# discferret_main.net
KiCad netlist of a schematic drawn in EAGLE
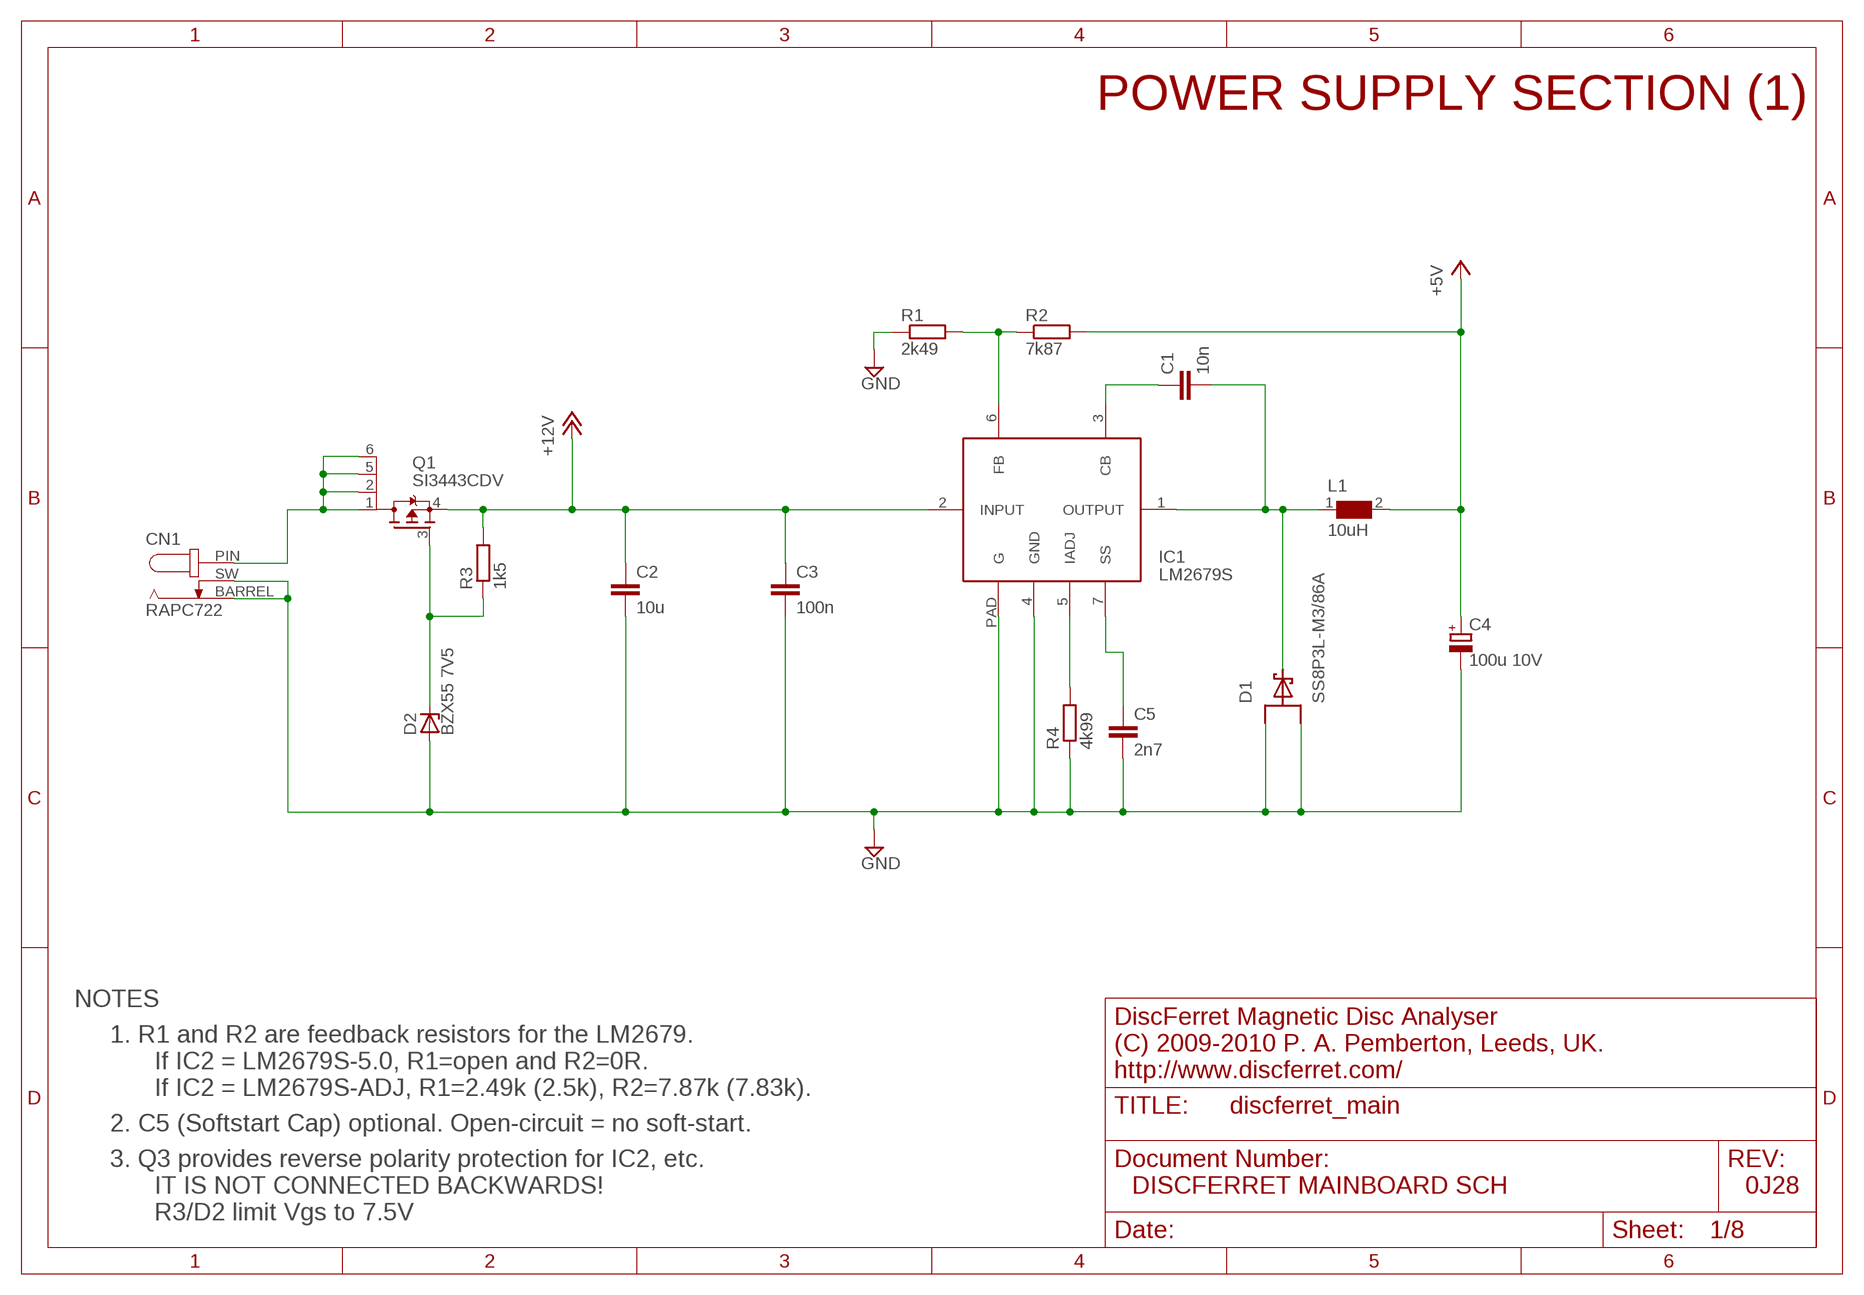
[diagram p0: schematic, sheet 1]
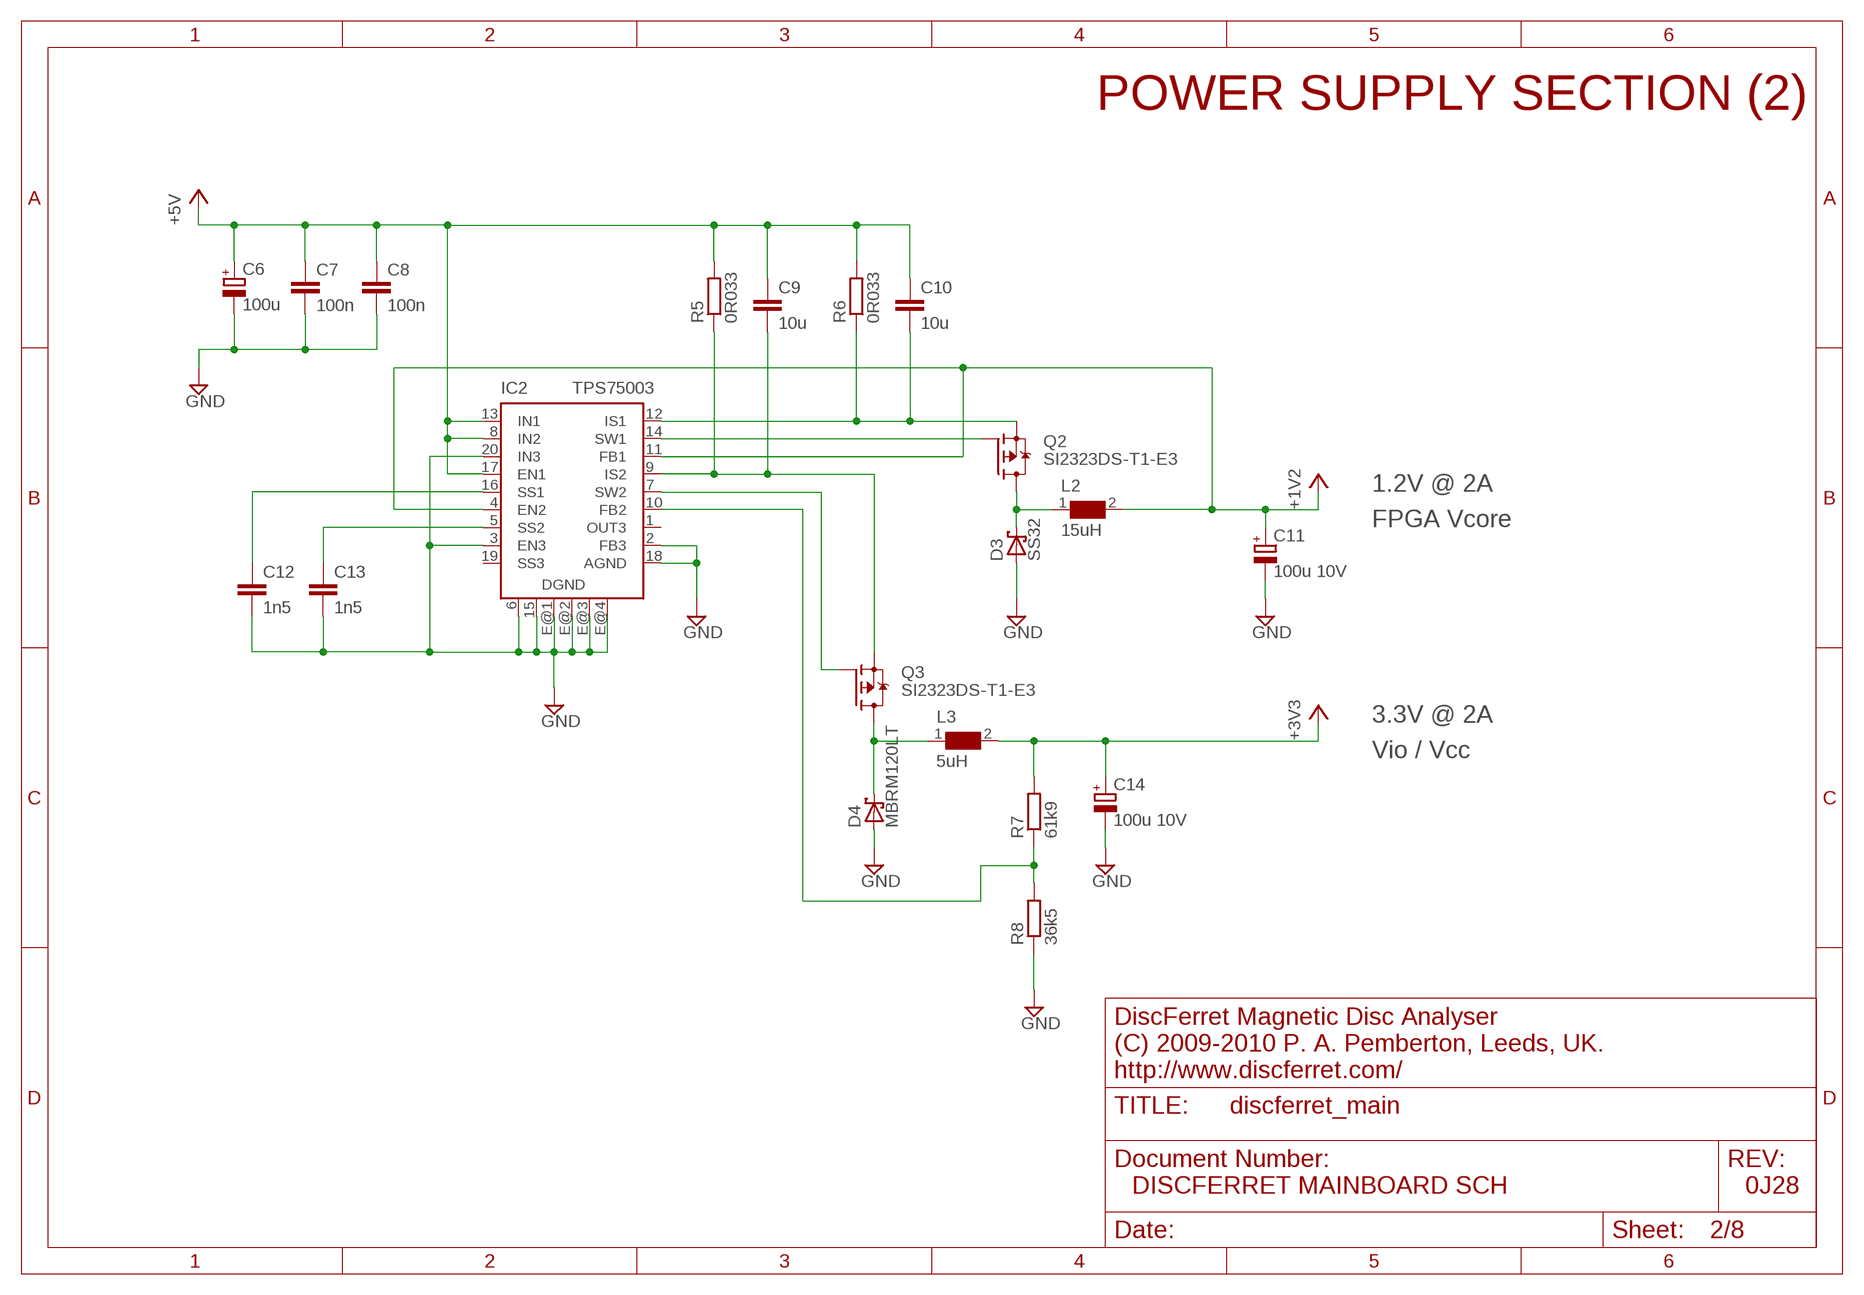
[diagram p1: schematic, sheet 2]
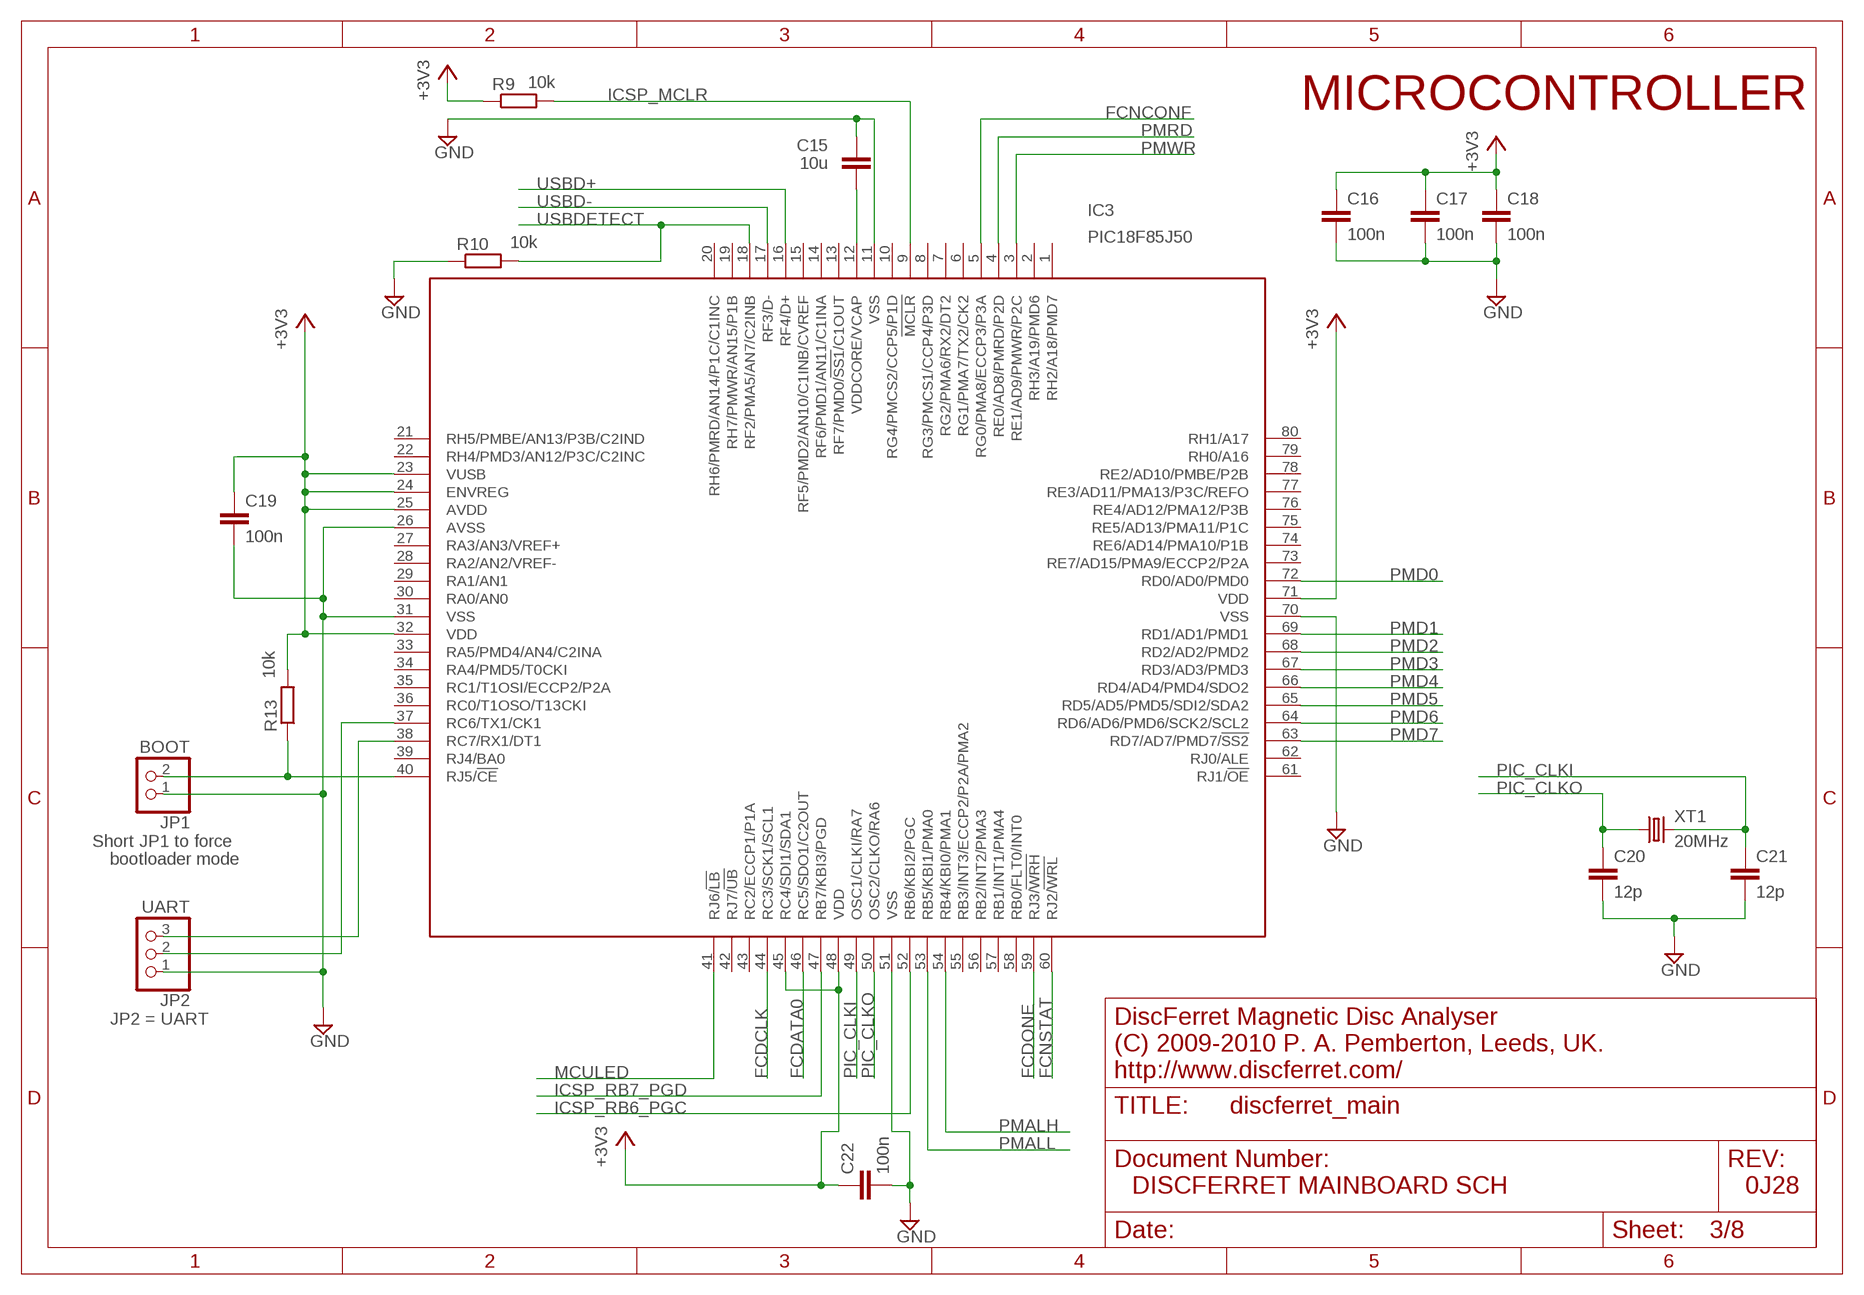
[diagram p2: schematic, sheet 3]
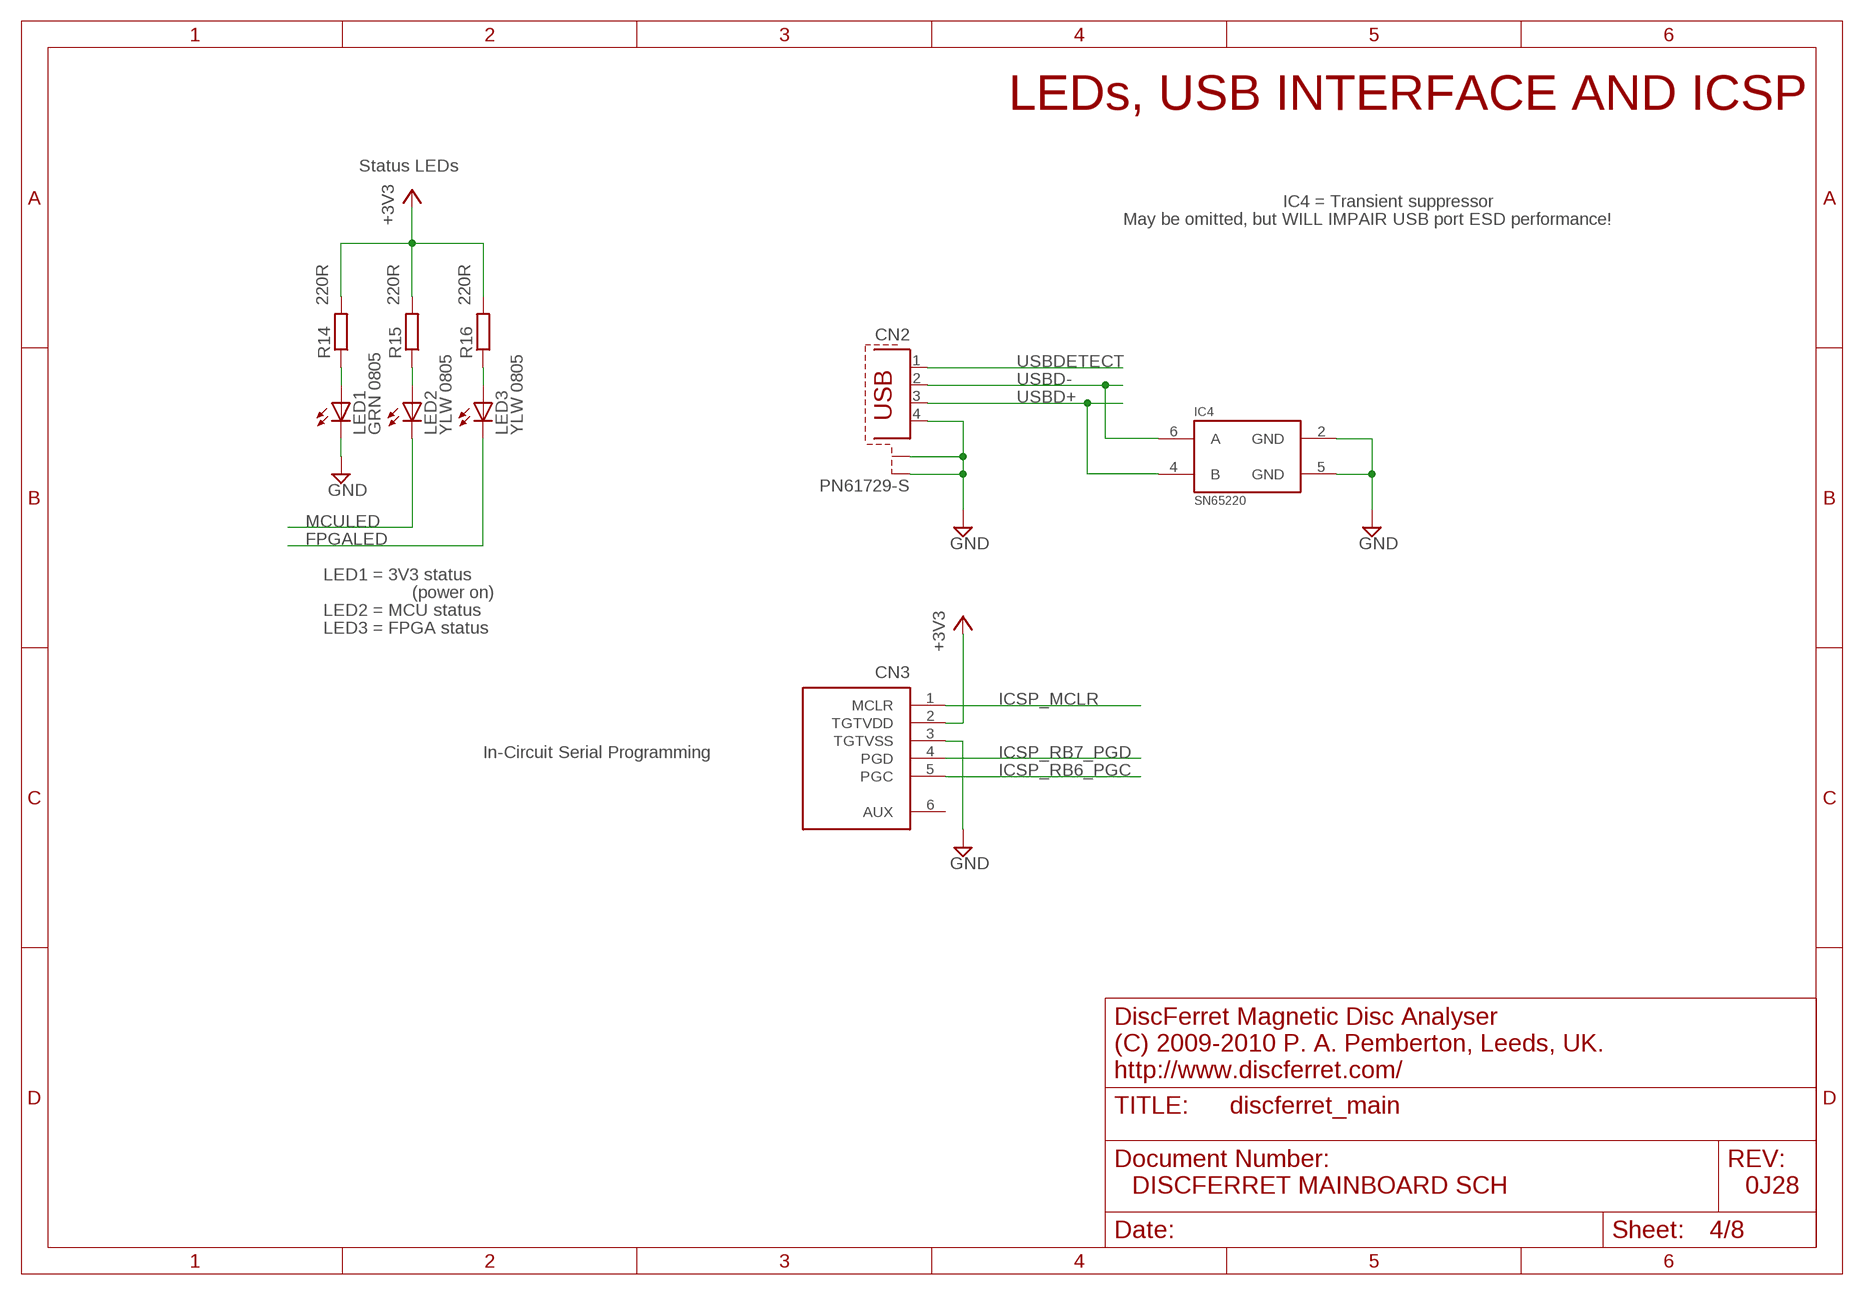
[diagram p3: schematic, sheet 4]
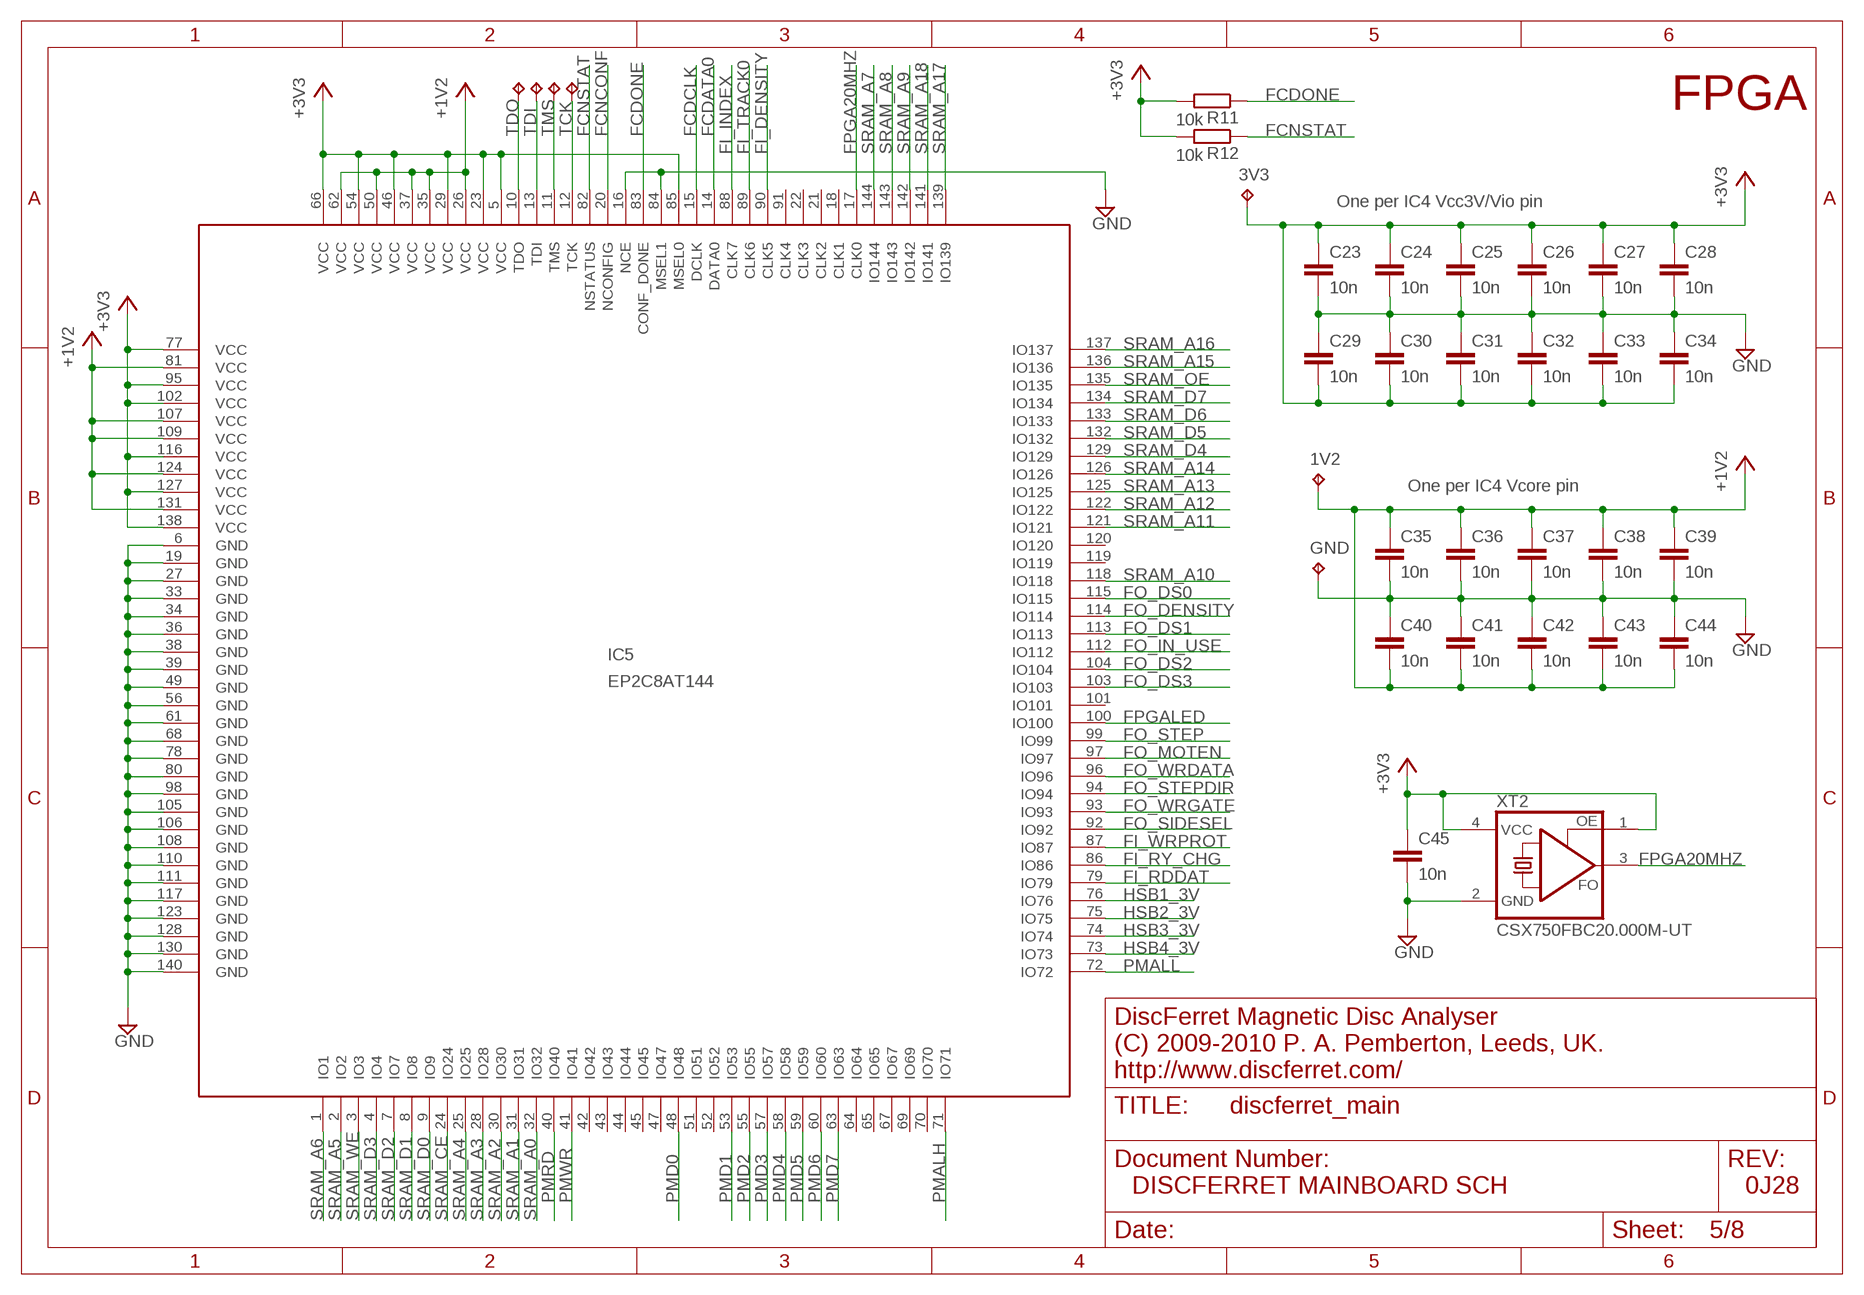
[diagram p4: schematic, sheet 5]
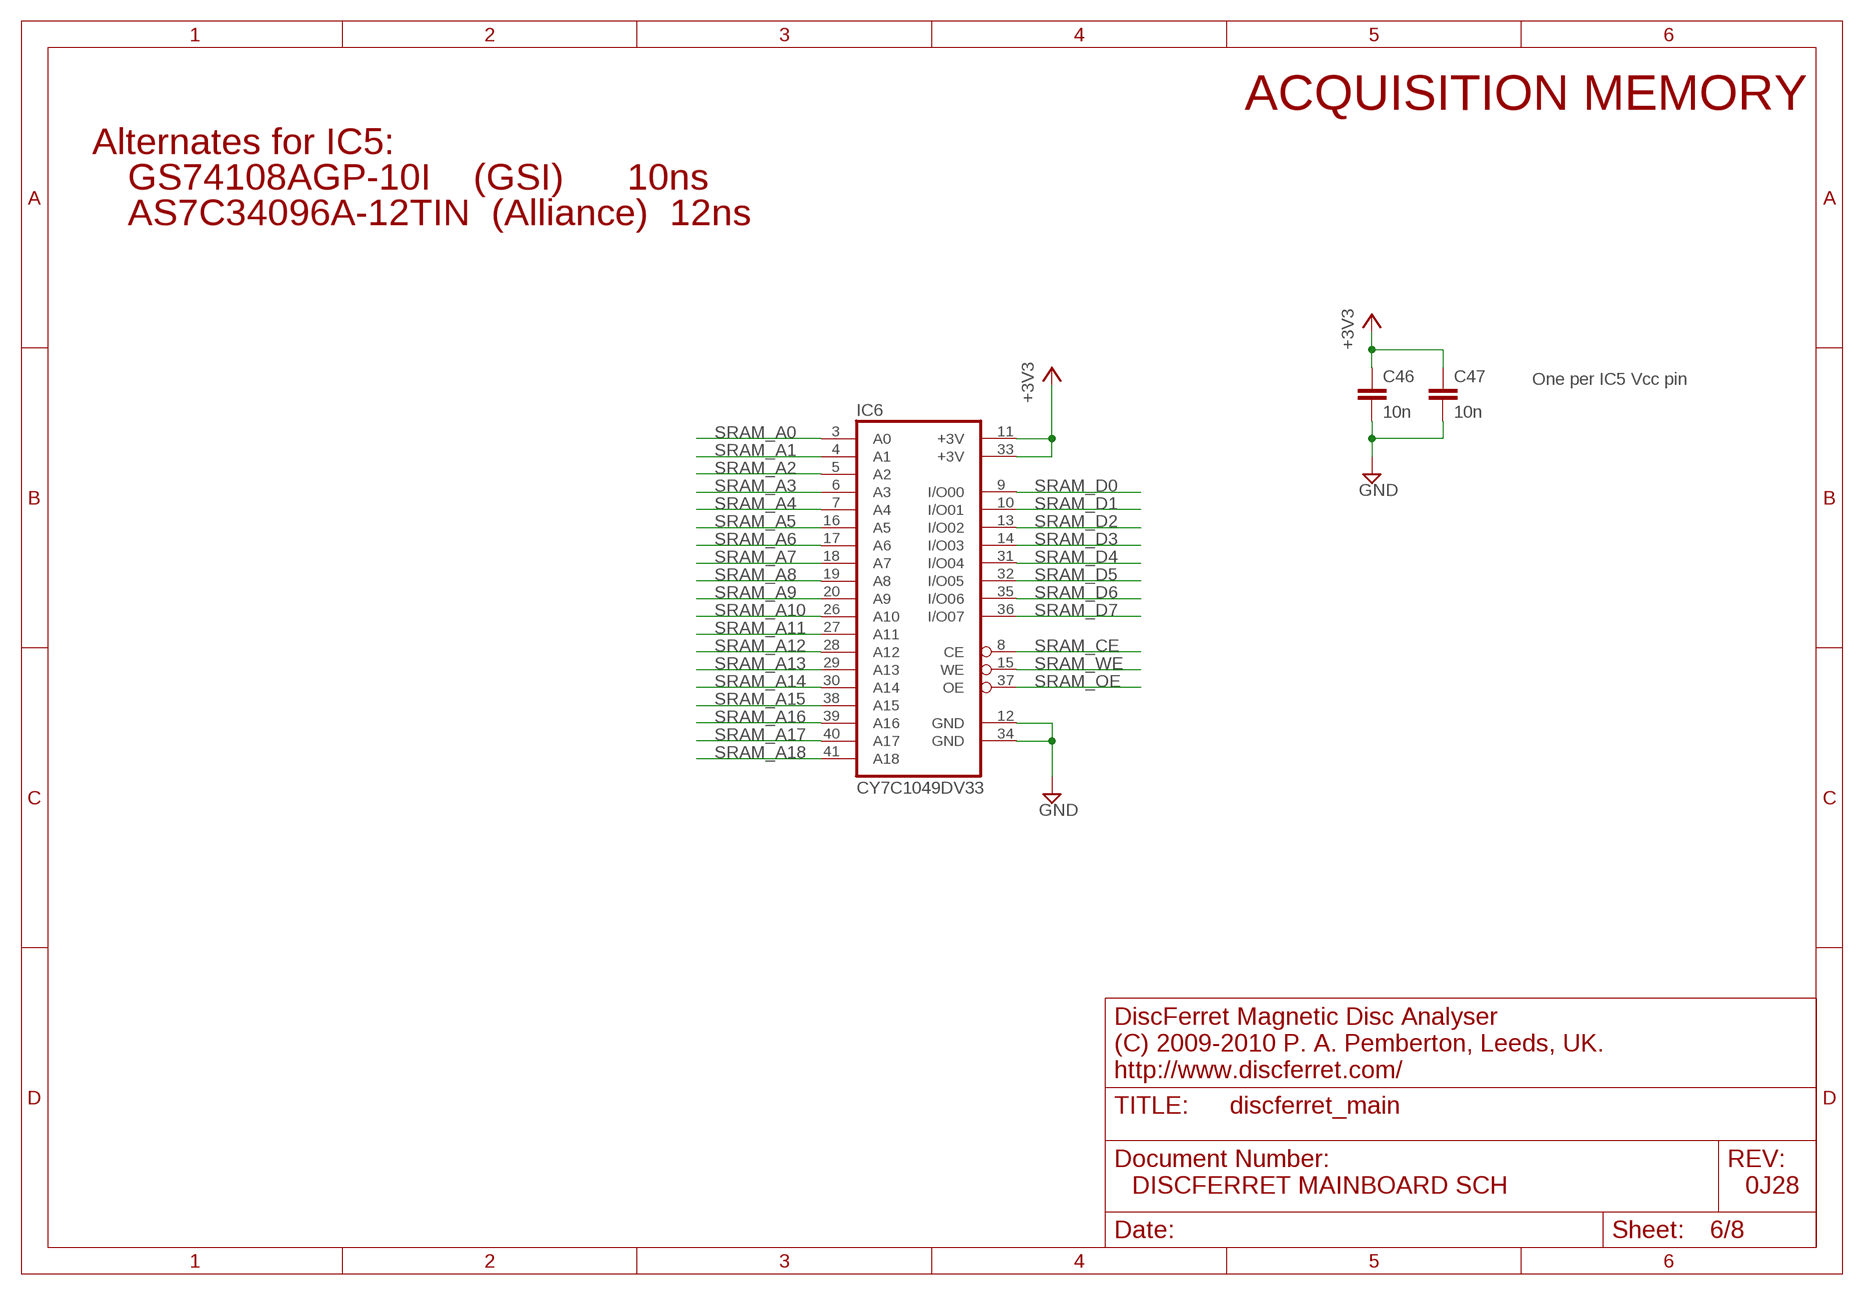
[diagram p5: schematic, sheet 6]
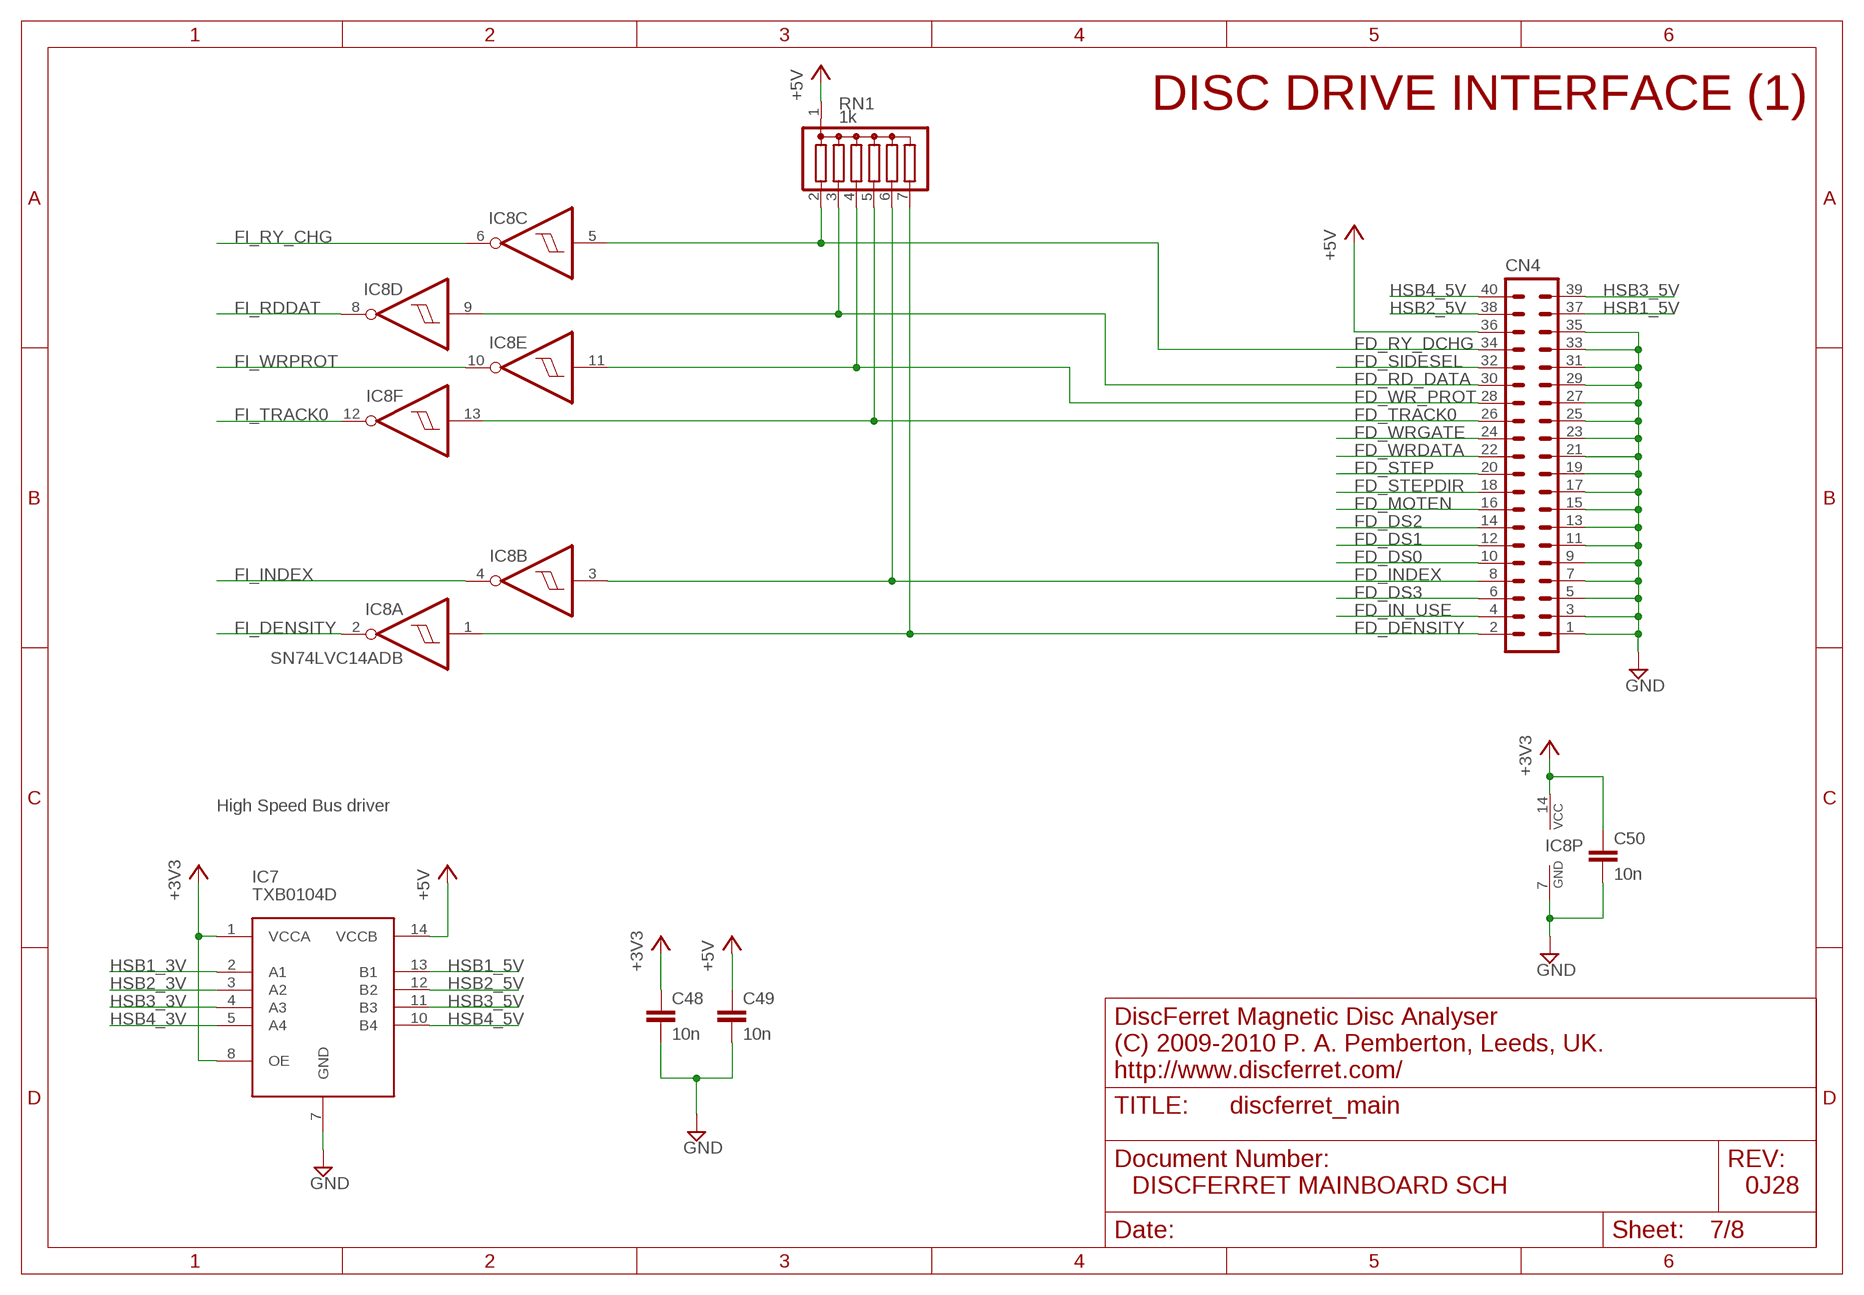
[diagram p6: schematic, sheet 7]
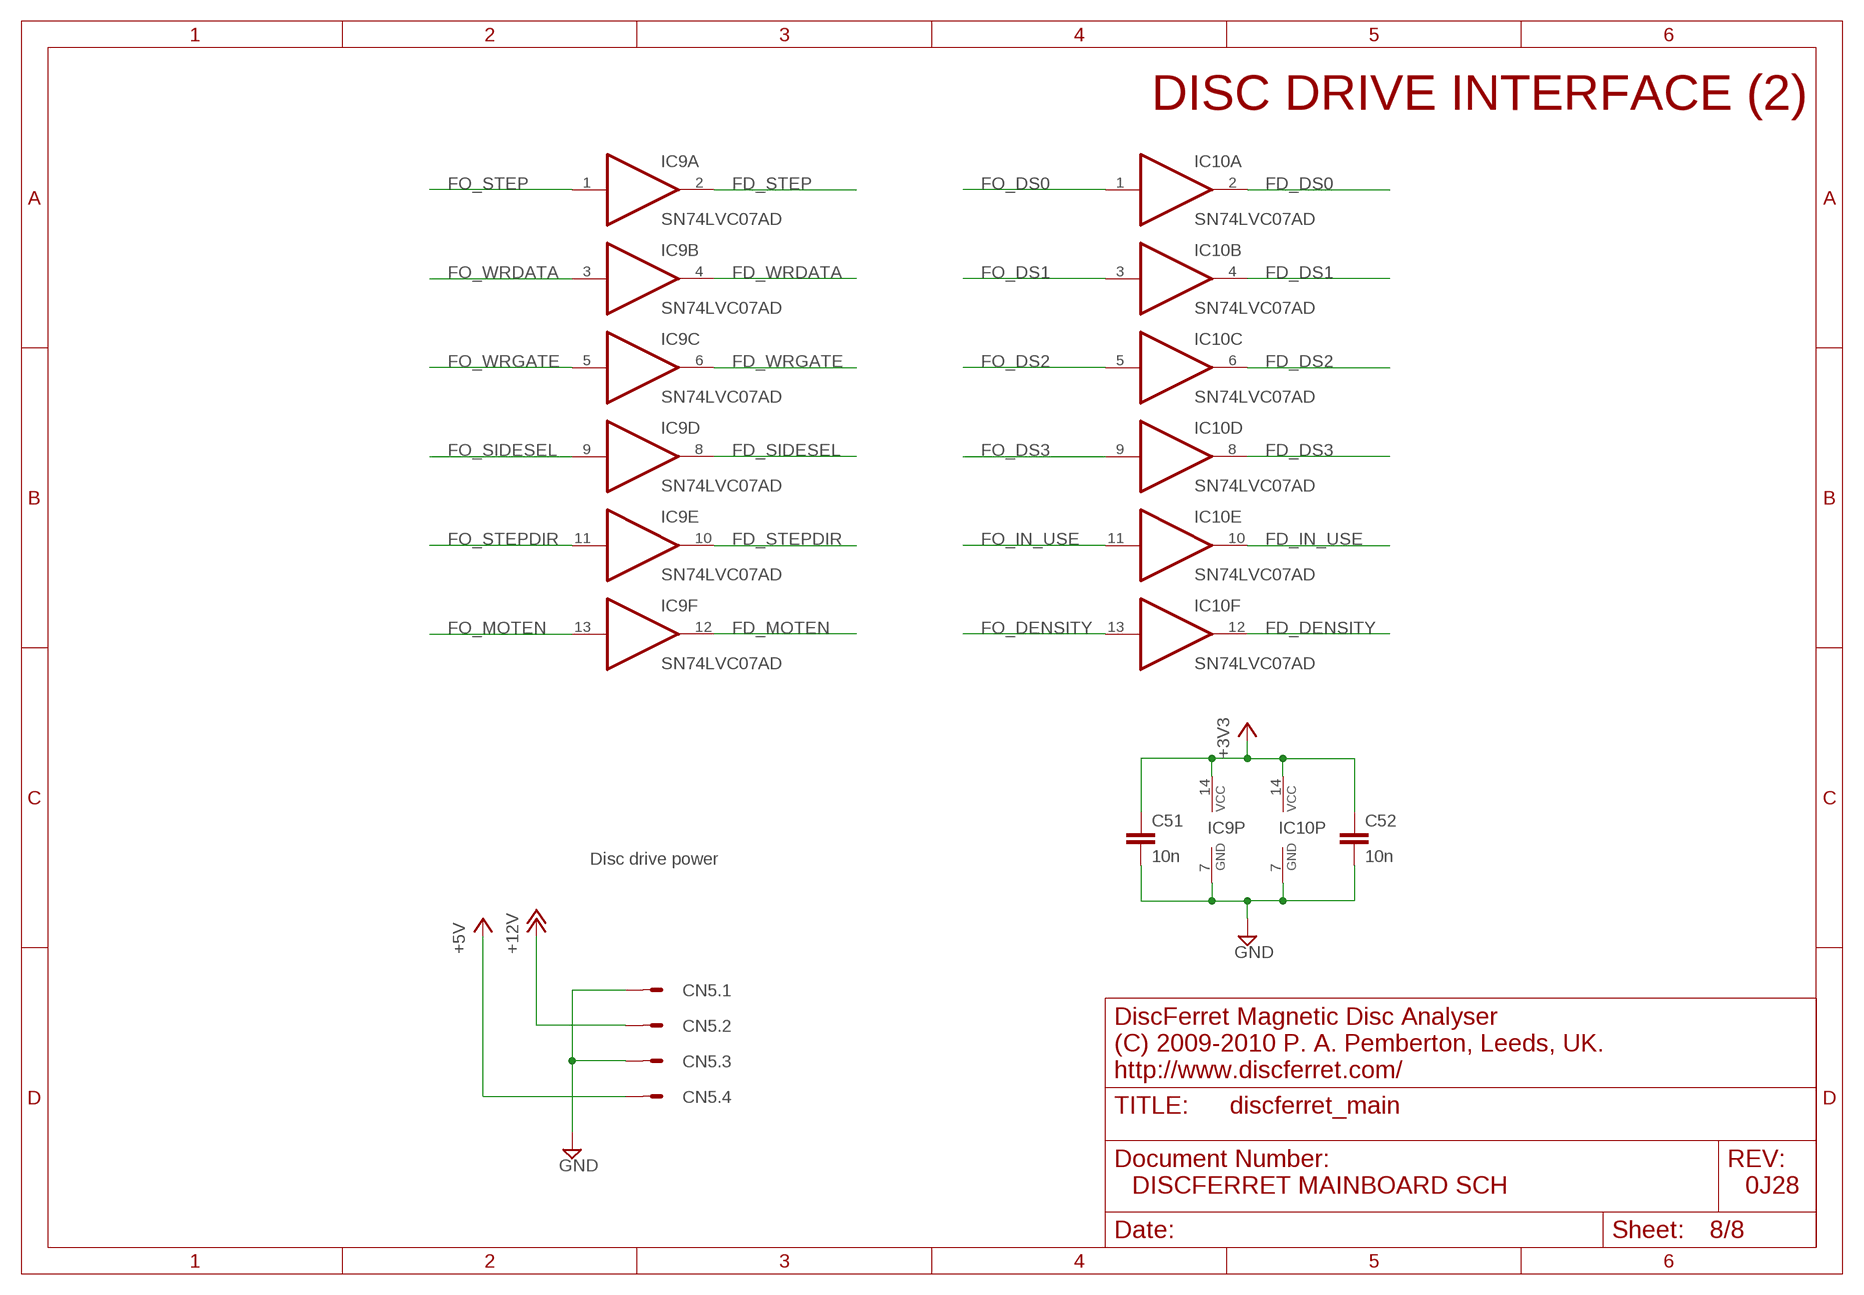
[diagram p7: schematic, sheet 8]

(export (version "E")
  (design (tool "Eeschema 10.0.6"))
  (components
    (comp (ref "C46")
      (value "10n")
      (footprint "eagle-import:C0603")
      (libsource (lib "eagle-import") (part "C-EUC0603"))
    )
    (comp (ref "C47")
      (value "10n")
      (footprint "eagle-import:C0603")
      (libsource (lib "eagle-import") (part "C-EUC0603"))
    )
    (comp (ref "IC6")
      (value "CY7C1049DV33")
      (footprint "eagle-import:TSOPII-Z44")
      (fields (field (name "MANUFACTURER") "Cypress Semiconductor"))
      (libsource (lib "eagle-import") (part "CY7C1049CV33T"))
    )
    (comp (ref "C48")
      (value "10n")
      (footprint "eagle-import:C0603")
      (libsource (lib "eagle-import") (part "C-EUC0603"))
    )
    (comp (ref "C49")
      (value "10n")
      (footprint "eagle-import:C0603")
      (libsource (lib "eagle-import") (part "C-EUC0603"))
    )
    (comp (ref "C50")
      (value "10n")
      (footprint "eagle-import:C0603")
      (libsource (lib "eagle-import") (part "C-EUC0603"))
    )
    (comp (ref "CN4")
      (value "40H")
      (footprint "eagle-import:40H")
      (fields (field (name "MANUFACTURER") "Multicomp"))
      (libsource (lib "eagle-import") (part "40H"))
    )
    (comp (ref "IC7")
      (value "TXB0104D")
      (footprint "eagle-import:SO14")
      (fields (field (name "MANUFACTURER") "Texas Instruments"))
      (libsource (lib "eagle-import") (part "TXB0104D"))
    )
    (comp (ref "IC8")
      (value "SN74LVC14ADB")
      (footprint "eagle-import:SSOP14")
      (fields
        (field (name "MANUF-PN") "SN74LVC14ADB")
        (field (name "MANUFACTURER") "Texas Instruments")
        (field (name "SUPPLIER") "FARNELL")
        (field (name "SUPPLIER-PN") "1236311")
      )
      (libsource (lib "eagle-import") (part "SN74LVC14ADB"))
    )
    (comp (ref "RN1")
      (value "1k")
      (footprint "eagle-import:SIL7")
      (fields (field (name "MANUFACTURER") "Bourns"))
      (libsource (lib "eagle-import") (part "G06R"))
    )
    (comp (ref "C6")
      (value "100u")
      (footprint "eagle-import:SMC_D")
      (fields (field (name "MANUFACTURER") "Vishay Sprague"))
      (libsource (lib "eagle-import") (part "CPOL-EUSMCD"))
    )
    (comp (ref "C7")
      (value "100n")
      (footprint "eagle-import:C0805")
      (libsource (lib "eagle-import") (part "C-EUC0805"))
    )
    (comp (ref "C8")
      (value "100n")
      (footprint "eagle-import:C0805")
      (libsource (lib "eagle-import") (part "C-EUC0805"))
    )
    (comp (ref "C9")
      (value "10u")
      (footprint "eagle-import:C0805")
      (fields (field (name "MANUFACTURER") "Murata"))
      (libsource (lib "eagle-import") (part "C-EUC0805"))
    )
    (comp (ref "C10")
      (value "10u")
      (footprint "eagle-import:C0805")
      (fields (field (name "MANUFACTURER") "Murata"))
      (libsource (lib "eagle-import") (part "C-EUC0805"))
    )
    (comp (ref "C11")
      (value "100u 10V")
      (footprint "eagle-import:SMC_D")
      (fields (field (name "MANUFACTURER") "AVX"))
      (libsource (lib "eagle-import") (part "CPOL-EUSMCD"))
    )
    (comp (ref "C12")
      (value "1n5")
      (footprint "eagle-import:C0805")
      (fields (field (name "MANUFACTURER") "Multicomp"))
      (libsource (lib "eagle-import") (part "C-EUC0805"))
    )
    (comp (ref "C13")
      (value "1n5")
      (footprint "eagle-import:C0805")
      (fields (field (name "MANUFACTURER") "Multicomp"))
      (libsource (lib "eagle-import") (part "C-EUC0805"))
    )
    (comp (ref "C14")
      (value "100u 10V")
      (footprint "eagle-import:SMC_D")
      (fields (field (name "MANUFACTURER") "AVX"))
      (libsource (lib "eagle-import") (part "CPOL-EUSMCD"))
    )
    (comp (ref "D3")
      (value "SS32")
      (footprint "eagle-import:SMC")
      (fields (field (name "MANUFACTURER") "Multicomp"))
      (libsource (lib "eagle-import") (part "SCHOTTKY-DIODESMC"))
    )
    (comp (ref "D4")
      (value "MBRM120LT")
      (footprint "eagle-import:POWERMITE_LARGEPAD")
      (fields (field (name "MANUFACTURER") "ON Semiconductor"))
      (libsource (lib "eagle-import") (part "MBRM120LT-LARGEPAD"))
    )
    (comp (ref "IC2")
      (value "TPS75003")
      (footprint "eagle-import:R-PQFP-N20")
      (fields (field (name "MANUFACTURER") "Texas Instruments"))
      (libsource (lib "eagle-import") (part "TPS75003"))
    )
    (comp (ref "L2")
      (value "15uH")
      (footprint "eagle-import:WE-TPC_XL_XLH")
      (fields (field (name "MANUFACTURER") "Bourns"))
      (libsource (lib "eagle-import") (part "WE-TPC_XL/XLH"))
    )
    (comp (ref "L3")
      (value "5uH")
      (footprint "eagle-import:WE-TPC_XL_XLH")
      (fields (field (name "MANUFACTURER") "Wuerth Elektronik"))
      (libsource (lib "eagle-import") (part "WE-TPC_XL/XLH"))
    )
    (comp (ref "Q2")
      (value "SI2323DS-T1-E3")
      (footprint "eagle-import:SOT23")
      (fields (field (name "MANUFACTURER") "Vishay Siliconix"))
      (libsource (lib "eagle-import") (part "SI2323DS-T1-E3"))
    )
    (comp (ref "Q3")
      (value "SI2323DS-T1-E3")
      (footprint "eagle-import:SOT23")
      (fields (field (name "MANUFACTURER") "Vishay Siliconix"))
      (libsource (lib "eagle-import") (part "SI2323DS-T1-E3"))
    )
    (comp (ref "R5")
      (value "0R033")
      (footprint "eagle-import:R1206")
      (fields (field (name "MANUFACTURER") "Welwyn"))
      (libsource (lib "eagle-import") (part "R-EU_R1206"))
    )
    (comp (ref "R6")
      (value "0R033")
      (footprint "eagle-import:R1206")
      (fields (field (name "MANUFACTURER") "Welwyn"))
      (libsource (lib "eagle-import") (part "R-EU_R1206"))
    )
    (comp (ref "R7")
      (value "61k9")
      (footprint "eagle-import:R0805")
      (libsource (lib "eagle-import") (part "R-EU_R0805"))
    )
    (comp (ref "R8")
      (value "36k5")
      (footprint "eagle-import:R0603")
      (libsource (lib "eagle-import") (part "R-EU_R0603"))
    )
    (comp (ref "C51")
      (value "10n")
      (footprint "eagle-import:C0603")
      (libsource (lib "eagle-import") (part "C-EUC0603"))
    )
    (comp (ref "C52")
      (value "10n")
      (footprint "eagle-import:C0603")
      (libsource (lib "eagle-import") (part "C-EUC0603"))
    )
    (comp (ref "CN5")
      (value "2X2-A")
      (footprint "eagle-import:3-794618-4")
      (libsource (lib "eagle-import") (part "2X2-A"))
    )
    (comp (ref "IC9")
      (value "SN74LVC07AD")
      (footprint "eagle-import:SO14")
      (fields
        (field (name "MANUFACTURER") "Texas Instruments")
        (field (name "SUPPLIER") "FARNELL")
        (field (name "SUPPLIER-PN") "9592660")
        (field (name "MANUF-PN") "SN74LVC07AD")
      )
      (libsource (lib "eagle-import") (part "SN74LVC07AD"))
    )
    (comp (ref "IC10")
      (value "SN74LVC07AD")
      (footprint "eagle-import:SO14")
      (fields
        (field (name "MANUF-PN") "SN74LVC07AD")
        (field (name "MANUFACTURER") "Texas Instruments")
        (field (name "SUPPLIER") "FARNELL")
        (field (name "SUPPLIER-PN") "9592660")
      )
      (libsource (lib "eagle-import") (part "SN74LVC07AD"))
    )
    (comp (ref "C15")
      (value "10u")
      (footprint "eagle-import:C0805")
      (fields (field (name "MANUFACTURER") "Murata"))
      (libsource (lib "eagle-import") (part "C-EUC0805"))
    )
    (comp (ref "C16")
      (value "100n")
      (footprint "eagle-import:C0603")
      (libsource (lib "eagle-import") (part "C-EUC0603"))
    )
    (comp (ref "C17")
      (value "100n")
      (footprint "eagle-import:C0603")
      (libsource (lib "eagle-import") (part "C-EUC0603"))
    )
    (comp (ref "C18")
      (value "100n")
      (footprint "eagle-import:C0603")
      (libsource (lib "eagle-import") (part "C-EUC0603"))
    )
    (comp (ref "C19")
      (value "100n")
      (footprint "eagle-import:C0603")
      (libsource (lib "eagle-import") (part "C-EUC0603"))
    )
    (comp (ref "C20")
      (value "12p")
      (footprint "eagle-import:C0603")
      (libsource (lib "eagle-import") (part "C-EUC0603"))
    )
    (comp (ref "C21")
      (value "12p")
      (footprint "eagle-import:C0603")
      (libsource (lib "eagle-import") (part "C-EUC0603"))
    )
    (comp (ref "C22")
      (value "100n")
      (footprint "eagle-import:C0603")
      (libsource (lib "eagle-import") (part "C-EUC0603"))
    )
    (comp (ref "IC3")
      (value "PIC18F85J50")
      (footprint "eagle-import:TQFP80-12X12")
      (libsource (lib "eagle-import") (part "PIC18F8J505"))
    )
    (comp (ref "JP1")
      (value "BOOT")
      (footprint "eagle-import:1X02")
      (libsource (lib "eagle-import") (part "PINHD-1X2"))
    )
    (comp (ref "JP2")
      (value "UART")
      (footprint "eagle-import:1X03")
      (libsource (lib "eagle-import") (part "PINHD-1X3"))
    )
    (comp (ref "R9")
      (value "10k")
      (footprint "eagle-import:R0805")
      (libsource (lib "eagle-import") (part "R-EU_R0805"))
    )
    (comp (ref "R10")
      (value "10k")
      (footprint "eagle-import:R0805")
      (libsource (lib "eagle-import") (part "R-EU_R0805"))
    )
    (comp (ref "R13")
      (value "10k")
      (footprint "eagle-import:R0805")
      (libsource (lib "eagle-import") (part "R-EU_R0805"))
    )
    (comp (ref "XT1")
      (value "20MHz")
      (footprint "eagle-import:HC49_S")
      (fields (field (name "MANUFACTURER") "Abracon"))
      (libsource (lib "eagle-import") (part "CRYSTALHC49S"))
    )
    (comp (ref "1V2")
      (value "TPB1,27")
      (footprint "eagle-import:B1,27")
      (libsource (lib "eagle-import") (part "TPB1,27"))
    )
    (comp (ref "3V3")
      (value "TPB1,27")
      (footprint "eagle-import:B1,27")
      (libsource (lib "eagle-import") (part "TPB1,27"))
    )
    (comp (ref "C23")
      (value "10n")
      (footprint "eagle-import:C0603")
      (libsource (lib "eagle-import") (part "C-EUC0603"))
    )
    (comp (ref "C24")
      (value "10n")
      (footprint "eagle-import:C0603")
      (libsource (lib "eagle-import") (part "C-EUC0603"))
    )
    (comp (ref "C25")
      (value "10n")
      (footprint "eagle-import:C0603")
      (libsource (lib "eagle-import") (part "C-EUC0603"))
    )
    (comp (ref "C26")
      (value "10n")
      (footprint "eagle-import:C0603")
      (libsource (lib "eagle-import") (part "C-EUC0603"))
    )
    (comp (ref "C27")
      (value "10n")
      (footprint "eagle-import:C0603")
      (libsource (lib "eagle-import") (part "C-EUC0603"))
    )
    (comp (ref "C28")
      (value "10n")
      (footprint "eagle-import:C0603")
      (libsource (lib "eagle-import") (part "C-EUC0603"))
    )
    (comp (ref "C29")
      (value "10n")
      (footprint "eagle-import:C0603")
      (libsource (lib "eagle-import") (part "C-EUC0603"))
    )
    (comp (ref "C30")
      (value "10n")
      (footprint "eagle-import:C0603")
      (libsource (lib "eagle-import") (part "C-EUC0603"))
    )
    (comp (ref "C31")
      (value "10n")
      (footprint "eagle-import:C0603")
      (libsource (lib "eagle-import") (part "C-EUC0603"))
    )
    (comp (ref "C32")
      (value "10n")
      (footprint "eagle-import:C0603")
      (libsource (lib "eagle-import") (part "C-EUC0603"))
    )
    (comp (ref "C33")
      (value "10n")
      (footprint "eagle-import:C0603")
      (libsource (lib "eagle-import") (part "C-EUC0603"))
    )
    (comp (ref "C34")
      (value "10n")
      (footprint "eagle-import:C0603")
      (libsource (lib "eagle-import") (part "C-EUC0603"))
    )
    (comp (ref "C35")
      (value "10n")
      (footprint "eagle-import:C0603")
      (libsource (lib "eagle-import") (part "C-EUC0603"))
    )
    (comp (ref "C36")
      (value "10n")
      (footprint "eagle-import:C0603")
      (libsource (lib "eagle-import") (part "C-EUC0603"))
    )
    (comp (ref "C37")
      (value "10n")
      (footprint "eagle-import:C0603")
      (libsource (lib "eagle-import") (part "C-EUC0603"))
    )
    (comp (ref "C38")
      (value "10n")
      (footprint "eagle-import:C0603")
      (libsource (lib "eagle-import") (part "C-EUC0603"))
    )
    (comp (ref "C39")
      (value "10n")
      (footprint "eagle-import:C0603")
      (libsource (lib "eagle-import") (part "C-EUC0603"))
    )
    (comp (ref "C40")
      (value "10n")
      (footprint "eagle-import:C0603")
      (libsource (lib "eagle-import") (part "C-EUC0603"))
    )
    (comp (ref "C41")
      (value "10n")
      (footprint "eagle-import:C0603")
      (libsource (lib "eagle-import") (part "C-EUC0603"))
    )
    (comp (ref "C42")
      (value "10n")
      (footprint "eagle-import:C0603")
      (libsource (lib "eagle-import") (part "C-EUC0603"))
    )
    (comp (ref "C43")
      (value "10n")
      (footprint "eagle-import:C0603")
      (libsource (lib "eagle-import") (part "C-EUC0603"))
    )
    (comp (ref "C44")
      (value "10n")
      (footprint "eagle-import:C0603")
      (libsource (lib "eagle-import") (part "C-EUC0603"))
    )
    (comp (ref "C45")
      (value "10n")
      (footprint "eagle-import:C0603")
      (libsource (lib "eagle-import") (part "C-EUC0603"))
    )
    (comp (ref "GND")
      (value "TPB1,27")
      (footprint "eagle-import:B1,27")
      (libsource (lib "eagle-import") (part "TPB1,27"))
    )
    (comp (ref "IC5")
      (value "EP2C8AT144")
      (footprint "eagle-import:TQFP144")
      (fields (field (name "MANUFACTURER") "Altera"))
      (libsource (lib "eagle-import") (part "EP2C8AT144"))
    )
    (comp (ref "R11")
      (value "10k")
      (footprint "eagle-import:R0805")
      (libsource (lib "eagle-import") (part "R-EU_R0805"))
    )
    (comp (ref "R12")
      (value "10k")
      (footprint "eagle-import:R0805")
      (libsource (lib "eagle-import") (part "R-EU_R0805"))
    )
    (comp (ref "TCK")
      (value "TPB1,27")
      (footprint "eagle-import:B1,27")
      (libsource (lib "eagle-import") (part "TPB1,27"))
    )
    (comp (ref "TDI")
      (value "TPB1,27")
      (footprint "eagle-import:B1,27")
      (libsource (lib "eagle-import") (part "TPB1,27"))
    )
    (comp (ref "TDO")
      (value "TPB1,27")
      (footprint "eagle-import:B1,27")
      (libsource (lib "eagle-import") (part "TPB1,27"))
    )
    (comp (ref "TMS")
      (value "TPB1,27")
      (footprint "eagle-import:B1,27")
      (libsource (lib "eagle-import") (part "TPB1,27"))
    )
    (comp (ref "XT2")
      (value "CSX750FBC20.000M-UT")
      (footprint "eagle-import:CSX750F")
      (fields (field (name "MANUFACTURER") "Citizen America"))
      (libsource (lib "eagle-import") (part "CSX750F"))
    )
    (comp (ref "CN2")
      (value "PN61729-S")
      (footprint "eagle-import:PN61729-S")
      (libsource (lib "eagle-import") (part "PN61729-S"))
    )
    (comp (ref "CN3")
      (value "ICSPSMD")
      (footprint "eagle-import:ICSP_SMD")
      (libsource (lib "eagle-import") (part "ICSPSMD"))
    )
    (comp (ref "IC4")
      (value "SN65220")
      (footprint "eagle-import:SOT23-6L")
      (fields (field (name "MANUFACTURER") "Texas Instruments"))
      (libsource (lib "eagle-import") (part "SN65220"))
    )
    (comp (ref "LED1")
      (value "GRN 0805")
      (footprint "eagle-import:CHIPLED_0805")
      (fields (field (name "MANUFACTURER") "Dialight Corporation"))
      (libsource (lib "eagle-import") (part "LEDCHIPLED_0805"))
    )
    (comp (ref "LED2")
      (value "YLW 0805")
      (footprint "eagle-import:CHIPLED_0805")
      (fields (field (name "MANUFACTURER") "Dialight Corporation"))
      (libsource (lib "eagle-import") (part "LEDCHIPLED_0805"))
    )
    (comp (ref "LED3")
      (value "YLW 0805")
      (footprint "eagle-import:CHIPLED_0805")
      (fields (field (name "MANUFACTURER") "Dialight Corporation"))
      (libsource (lib "eagle-import") (part "LEDCHIPLED_0805"))
    )
    (comp (ref "R14")
      (value "220R")
      (footprint "eagle-import:R0805")
      (libsource (lib "eagle-import") (part "R-EU_R0805"))
    )
    (comp (ref "R15")
      (value "220R")
      (footprint "eagle-import:R0805")
      (libsource (lib "eagle-import") (part "R-EU_R0805"))
    )
    (comp (ref "R16")
      (value "220R")
      (footprint "eagle-import:R0805")
      (libsource (lib "eagle-import") (part "R-EU_R0805"))
    )
    (comp (ref "C1")
      (value "10n")
      (footprint "eagle-import:C0603")
      (libsource (lib "eagle-import") (part "C-EUC0603"))
    )
    (comp (ref "C2")
      (value "10u")
      (footprint "eagle-import:C0805")
      (fields (field (name "MANUFACTURER") "Murata"))
      (libsource (lib "eagle-import") (part "C-EUC0805"))
    )
    (comp (ref "C3")
      (value "100n")
      (footprint "eagle-import:C0603")
      (libsource (lib "eagle-import") (part "C-EUC0603"))
    )
    (comp (ref "C4")
      (value "100u 10V")
      (footprint "eagle-import:SMC_D")
      (fields (field (name "MANUFACTURER") "AVX"))
      (libsource (lib "eagle-import") (part "CPOL-EUSMCD"))
    )
    (comp (ref "C5")
      (value "2n7")
      (footprint "eagle-import:C0805")
      (libsource (lib "eagle-import") (part "C-EUC0805"))
    )
    (comp (ref "CN1")
      (value "RAPC722")
      (footprint "eagle-import:RAPC722NT")
      (fields (field (name "MANUFACTURER") "Switchcraft"))
      (libsource (lib "eagle-import") (part "RAPC722_NO_THERMALS"))
    )
    (comp (ref "D1")
      (value "SS8P3L-M3/86A")
      (footprint "eagle-import:TO277A_SMPC_LARGEPAD")
      (fields (field (name "MANUFACTURER") "Vishay General Semiconductor"))
      (libsource (lib "eagle-import") (part "SS8PH9-LARGEPAD"))
    )
    (comp (ref "D2")
      (value "BZX55 7V5")
      (footprint "eagle-import:DO35Z10")
      (libsource (lib "eagle-import") (part "BZX55"))
    )
    (comp (ref "IC1")
      (value "LM2679S")
      (footprint "eagle-import:TO263-7")
      (fields (field (name "MANUFACTURER") "National Semiconductor"))
      (libsource (lib "eagle-import") (part "LM2679"))
    )
    (comp (ref "L1")
      (value "10uH")
      (footprint "eagle-import:WE-PD_L_LS_XL_XXL")
      (fields (field (name "MANUFACTURER") "Wurth Elektronik"))
      (libsource (lib "eagle-import") (part "WE-PD_L/LS/XL/XXL"))
    )
    (comp (ref "Q1")
      (value "SI3443CDV")
      (footprint "eagle-import:TSOP6_VISHAY_LARGEPAD")
      (fields (field (name "MANUFACTURER") "Vishay"))
      (libsource (lib "eagle-import") (part "SI3443CDV-LARGEPAD"))
    )
    (comp (ref "R1")
      (value "2k49")
      (footprint "eagle-import:R0805")
      (fields (field (name "MANUFACTURER") "Vishay Draloric"))
      (libsource (lib "eagle-import") (part "R-EU_R0805"))
    )
    (comp (ref "R2")
      (value "7k87")
      (footprint "eagle-import:R0805")
      (fields (field (name "MANUFACTURER") "Welwyn"))
      (libsource (lib "eagle-import") (part "R-EU_R0805"))
    )
    (comp (ref "R3")
      (value "1k5")
      (footprint "eagle-import:R0805")
      (fields (field (name "MANUFACTURER") "Multicomp"))
      (libsource (lib "eagle-import") (part "R-EU_R0805"))
    )
    (comp (ref "R4")
      (value "4k99")
      (footprint "eagle-import:R0805")
      (libsource (lib "eagle-import") (part "R-EU_R0805"))
    )
  )
  (nets
    (net (code "1") (name "+1V2") (class "Default")
      (node (ref "1V2") (pin "TP") (pinfunction "TP_TP") (pintype "input"))
      (node (ref "C11") (pin "+") (pinfunction "+_+") (pintype "passive"))
      (node (ref "C35") (pin "1") (pinfunction "1_1") (pintype "passive"))
      (node (ref "C36") (pin "1") (pinfunction "1_1") (pintype "passive"))
      (node (ref "C37") (pin "1") (pinfunction "1_1") (pintype "passive"))
      (node (ref "C38") (pin "1") (pinfunction "1_1") (pintype "passive"))
      (node (ref "C39") (pin "1") (pinfunction "1_1") (pintype "passive"))
      (node (ref "C40") (pin "2") (pinfunction "2_2") (pintype "passive"))
      (node (ref "C41") (pin "2") (pinfunction "2_2") (pintype "passive"))
      (node (ref "C42") (pin "2") (pinfunction "2_2") (pintype "passive"))
      (node (ref "C43") (pin "2") (pinfunction "2_2") (pintype "passive"))
      (node (ref "C44") (pin "2") (pinfunction "2_2") (pintype "passive"))
      (node (ref "IC2") (pin "11") (pinfunction "FB1_11") (pintype "input"))
      (node (ref "IC2") (pin "4") (pinfunction "EN2_4") (pintype "input"))
      (node (ref "IC5") (pin "107") (pinfunction "VCC_107") (pintype "power_in"))
      (node (ref "IC5") (pin "109") (pinfunction "VCC_109") (pintype "power_in"))
      (node (ref "IC5") (pin "124") (pinfunction "VCC_124") (pintype "power_in"))
      (node (ref "IC5") (pin "131") (pinfunction "VCC_131") (pintype "power_in"))
      (node (ref "IC5") (pin "26") (pinfunction "VCC_26") (pintype "power_in"))
      (node (ref "IC5") (pin "35") (pinfunction "VCC_35") (pintype "power_in"))
      (node (ref "IC5") (pin "37") (pinfunction "VCC_37") (pintype "power_in"))
      (node (ref "IC5") (pin "50") (pinfunction "VCC_50") (pintype "power_in"))
      (node (ref "IC5") (pin "62") (pinfunction "VCC_62") (pintype "power_in"))
      (node (ref "IC5") (pin "81") (pinfunction "VCC_81") (pintype "power_in"))
      (node (ref "L2") (pin "2") (pinfunction "2_2") (pintype "passive"))
    )
    (net (code "2") (name "+3V3") (class "Default")
      (node (ref "3V3") (pin "TP") (pinfunction "TP_TP") (pintype "input"))
      (node (ref "C14") (pin "+") (pinfunction "+_+") (pintype "passive"))
      (node (ref "C16") (pin "1") (pinfunction "1_1") (pintype "passive"))
      (node (ref "C17") (pin "1") (pinfunction "1_1") (pintype "passive"))
      (node (ref "C18") (pin "1") (pinfunction "1_1") (pintype "passive"))
      (node (ref "C19") (pin "1") (pinfunction "1_1") (pintype "passive"))
      (node (ref "C22") (pin "1") (pinfunction "1_1") (pintype "passive"))
      (node (ref "C23") (pin "1") (pinfunction "1_1") (pintype "passive"))
      (node (ref "C24") (pin "1") (pinfunction "1_1") (pintype "passive"))
      (node (ref "C25") (pin "1") (pinfunction "1_1") (pintype "passive"))
      (node (ref "C26") (pin "1") (pinfunction "1_1") (pintype "passive"))
      (node (ref "C27") (pin "1") (pinfunction "1_1") (pintype "passive"))
      (node (ref "C28") (pin "1") (pinfunction "1_1") (pintype "passive"))
      (node (ref "C29") (pin "2") (pinfunction "2_2") (pintype "passive"))
      (node (ref "C30") (pin "2") (pinfunction "2_2") (pintype "passive"))
      (node (ref "C31") (pin "2") (pinfunction "2_2") (pintype "passive"))
      (node (ref "C32") (pin "2") (pinfunction "2_2") (pintype "passive"))
      (node (ref "C33") (pin "2") (pinfunction "2_2") (pintype "passive"))
      (node (ref "C34") (pin "2") (pinfunction "2_2") (pintype "passive"))
      (node (ref "C45") (pin "1") (pinfunction "1_1") (pintype "passive"))
      (node (ref "C46") (pin "1") (pinfunction "1_1") (pintype "passive"))
      (node (ref "C47") (pin "1") (pinfunction "1_1") (pintype "passive"))
      (node (ref "C48") (pin "1") (pinfunction "1_1") (pintype "passive"))
      (node (ref "C50") (pin "1") (pinfunction "1_1") (pintype "passive"))
      (node (ref "C51") (pin "1") (pinfunction "1_1") (pintype "passive"))
      (node (ref "C52") (pin "1") (pinfunction "1_1") (pintype "passive"))
      (node (ref "CN3") (pin "2") (pinfunction "TGTVDD_2") (pintype "bidirectional"))
      (node (ref "IC10") (pin "14") (pinfunction "VCC_14") (pintype "power_in"))
      (node (ref "IC3") (pin "23") (pinfunction "VUSB_23") (pintype "input"))
      (node (ref "IC3") (pin "24") (pinfunction "ENVREG_24") (pintype "input"))
      (node (ref "IC3") (pin "25") (pinfunction "AVDD_25") (pintype "bidirectional"))
      (node (ref "IC3") (pin "32") (pinfunction "VDD_32") (pintype "power_in"))
      (node (ref "IC3") (pin "45") (pinfunction "RC4/SDI1/SDA1_45") (pintype "bidirectional"))
      (node (ref "IC3") (pin "48") (pinfunction "VDD_48") (pintype "power_in"))
      (node (ref "IC3") (pin "71") (pinfunction "VDD_71") (pintype "power_in"))
      (node (ref "IC5") (pin "102") (pinfunction "VCC_102") (pintype "power_in"))
      (node (ref "IC5") (pin "116") (pinfunction "VCC_116") (pintype "power_in"))
      (node (ref "IC5") (pin "127") (pinfunction "VCC_127") (pintype "power_in"))
      (node (ref "IC5") (pin "138") (pinfunction "VCC_138") (pintype "power_in"))
      (node (ref "IC5") (pin "23") (pinfunction "VCC_23") (pintype "power_in"))
      (node (ref "IC5") (pin "29") (pinfunction "VCC_29") (pintype "power_in"))
      (node (ref "IC5") (pin "46") (pinfunction "VCC_46") (pintype "power_in"))
      (node (ref "IC5") (pin "5") (pinfunction "VCC_5") (pintype "power_in"))
      (node (ref "IC5") (pin "54") (pinfunction "VCC_54") (pintype "power_in"))
      (node (ref "IC5") (pin "66") (pinfunction "VCC_66") (pintype "power_in"))
      (node (ref "IC5") (pin "77") (pinfunction "VCC_77") (pintype "power_in"))
      (node (ref "IC5") (pin "85") (pinfunction "MSEL0_85") (pintype "input"))
      (node (ref "IC5") (pin "95") (pinfunction "VCC_95") (pintype "power_in"))
      (node (ref "IC6") (pin "11") (pinfunction "+3V_11") (pintype "power_in"))
      (node (ref "IC6") (pin "33") (pinfunction "+3V_33") (pintype "power_in"))
      (node (ref "IC7") (pin "1") (pinfunction "VCCA_1") (pintype "power_in"))
      (node (ref "IC7") (pin "8") (pinfunction "OE_8") (pintype "input"))
      (node (ref "IC8") (pin "14") (pinfunction "VCC_14") (pintype "power_in"))
      (node (ref "IC9") (pin "14") (pinfunction "VCC_14") (pintype "power_in"))
      (node (ref "L3") (pin "2") (pinfunction "2_2") (pintype "passive"))
      (node (ref "R11") (pin "2") (pinfunction "2_2") (pintype "passive"))
      (node (ref "R12") (pin "2") (pinfunction "2_2") (pintype "passive"))
      (node (ref "R13") (pin "2") (pinfunction "2_2") (pintype "passive"))
      (node (ref "R14") (pin "2") (pinfunction "2_2") (pintype "passive"))
      (node (ref "R15") (pin "2") (pinfunction "2_2") (pintype "passive"))
      (node (ref "R16") (pin "2") (pinfunction "2_2") (pintype "passive"))
      (node (ref "R7") (pin "2") (pinfunction "2_2") (pintype "passive"))
      (node (ref "R9") (pin "1") (pinfunction "1_1") (pintype "passive"))
      (node (ref "XT2") (pin "1") (pinfunction "OE_1") (pintype "input"))
      (node (ref "XT2") (pin "4") (pinfunction "VCC_4") (pintype "power_in"))
    )
    (net (code "3") (name "+5V") (class "Default")
      (node (ref "C10") (pin "1") (pinfunction "1_1") (pintype "passive"))
      (node (ref "C4") (pin "+") (pinfunction "+_+") (pintype "passive"))
      (node (ref "C49") (pin "1") (pinfunction "1_1") (pintype "passive"))
      (node (ref "C6") (pin "+") (pinfunction "+_+") (pintype "passive"))
      (node (ref "C7") (pin "1") (pinfunction "1_1") (pintype "passive"))
      (node (ref "C8") (pin "1") (pinfunction "1_1") (pintype "passive"))
      (node (ref "C9") (pin "1") (pinfunction "1_1") (pintype "passive"))
      (node (ref "CN4") (pin "36") (pinfunction "36_36") (pintype "passive"))
      (node (ref "CN5") (pin "4") (pinfunction "S_4") (pintype "passive"))
      (node (ref "IC2") (pin "13") (pinfunction "IN1_13") (pintype "input"))
      (node (ref "IC2") (pin "17") (pinfunction "EN1_17") (pintype "input"))
      (node (ref "IC2") (pin "8") (pinfunction "IN2_8") (pintype "input"))
      (node (ref "IC7") (pin "14") (pinfunction "VCCB_14") (pintype "power_in"))
      (node (ref "L1") (pin "2") (pinfunction "2_2") (pintype "passive"))
      (node (ref "R2") (pin "2") (pinfunction "2_2") (pintype "passive"))
      (node (ref "R5") (pin "2") (pinfunction "2_2") (pintype "passive"))
      (node (ref "R6") (pin "2") (pinfunction "2_2") (pintype "passive"))
      (node (ref "RN1") (pin "1") (pinfunction "1_1") (pintype "passive"))
    )
    (net (code "4") (name "+12V") (class "Default")
      (node (ref "C2") (pin "1") (pinfunction "1_1") (pintype "passive"))
      (node (ref "C3") (pin "1") (pinfunction "1_1") (pintype "passive"))
      (node (ref "CN5") (pin "2") (pinfunction "S_2") (pintype "passive"))
      (node (ref "IC1") (pin "2") (pinfunction "INPUT_2") (pintype "input"))
      (node (ref "Q1") (pin "4") (pinfunction "S_4") (pintype "passive"))
      (node (ref "R3") (pin "2") (pinfunction "2_2") (pintype "passive"))
    )
    (net (code "5") (name "FCDATA0") (class "Default")
      (node (ref "IC3") (pin "46") (pinfunction "RC5/SDO1/C2OUT_46") (pintype "bidirectional"))
      (node (ref "IC5") (pin "14") (pinfunction "DATA0_14") (pintype "bidirectional"))
    )
    (net (code "6") (name "FCDCLK") (class "Default")
      (node (ref "IC3") (pin "44") (pinfunction "RC3/SCK1/SCL1_44") (pintype "bidirectional"))
      (node (ref "IC5") (pin "15") (pinfunction "DCLK_15") (pintype "bidirectional"))
    )
    (net (code "7") (name "FCDONE") (class "Default")
      (node (ref "IC3") (pin "59") (pinfunction "RJ3/~{WRH}_59") (pintype "bidirectional"))
      (node (ref "IC5") (pin "83") (pinfunction "CONF_DONE_83") (pintype "input"))
      (node (ref "R11") (pin "1") (pinfunction "1_1") (pintype "passive"))
    )
    (net (code "8") (name "FCNCONF") (class "Default")
      (node (ref "IC3") (pin "5") (pinfunction "RG0/PMA8/ECCP3/P3A_5") (pintype "bidirectional"))
      (node (ref "IC5") (pin "20") (pinfunction "NCONFIG_20") (pintype "input"))
    )
    (net (code "9") (name "FCNSTAT") (class "Default")
      (node (ref "IC3") (pin "60") (pinfunction "RJ2/~{WRL}_60") (pintype "bidirectional"))
      (node (ref "IC5") (pin "82") (pinfunction "NSTATUS_82") (pintype "input"))
      (node (ref "R12") (pin "1") (pinfunction "1_1") (pintype "passive"))
    )
    (net (code "10") (name "FD_DENSITY") (class "Default")
      (node (ref "CN4") (pin "2") (pinfunction "2_2") (pintype "passive"))
      (node (ref "IC10") (pin "12") (pinfunction "O_12") (pintype "open_collector"))
      (node (ref "IC8") (pin "1") (pinfunction "I_1") (pintype "input"))
      (node (ref "RN1") (pin "7") (pinfunction "7_7") (pintype "passive"))
    )
    (net (code "11") (name "FD_DS0") (class "Default")
      (node (ref "CN4") (pin "10") (pinfunction "10_10") (pintype "passive"))
      (node (ref "IC10") (pin "2") (pinfunction "O_2") (pintype "open_collector"))
    )
    (net (code "12") (name "FD_DS1") (class "Default")
      (node (ref "CN4") (pin "12") (pinfunction "12_12") (pintype "passive"))
      (node (ref "IC10") (pin "4") (pinfunction "O_4") (pintype "open_collector"))
    )
    (net (code "13") (name "FD_DS2") (class "Default")
      (node (ref "CN4") (pin "14") (pinfunction "14_14") (pintype "passive"))
      (node (ref "IC10") (pin "6") (pinfunction "O_6") (pintype "open_collector"))
    )
    (net (code "14") (name "FD_DS3") (class "Default")
      (node (ref "CN4") (pin "6") (pinfunction "6_6") (pintype "passive"))
      (node (ref "IC10") (pin "8") (pinfunction "O_8") (pintype "open_collector"))
    )
    (net (code "15") (name "FD_INDEX") (class "Default")
      (node (ref "CN4") (pin "8") (pinfunction "8_8") (pintype "passive"))
      (node (ref "IC8") (pin "3") (pinfunction "I_3") (pintype "input"))
      (node (ref "RN1") (pin "6") (pinfunction "6_6") (pintype "passive"))
    )
    (net (code "16") (name "FD_IN_USE") (class "Default")
      (node (ref "CN4") (pin "4") (pinfunction "4_4") (pintype "passive"))
      (node (ref "IC10") (pin "10") (pinfunction "O_10") (pintype "open_collector"))
    )
    (net (code "17") (name "FD_MOTEN") (class "Default")
      (node (ref "CN4") (pin "16") (pinfunction "16_16") (pintype "passive"))
      (node (ref "IC9") (pin "12") (pinfunction "O_12") (pintype "open_collector"))
    )
    (net (code "18") (name "FD_RD_DATA") (class "Default")
      (node (ref "CN4") (pin "30") (pinfunction "30_30") (pintype "passive"))
      (node (ref "IC8") (pin "9") (pinfunction "I_9") (pintype "input"))
      (node (ref "RN1") (pin "3") (pinfunction "3_3") (pintype "passive"))
    )
    (net (code "19") (name "FD_RY_DCHG") (class "Default")
      (node (ref "CN4") (pin "34") (pinfunction "34_34") (pintype "passive"))
      (node (ref "IC8") (pin "5") (pinfunction "I_5") (pintype "input"))
      (node (ref "RN1") (pin "2") (pinfunction "2_2") (pintype "passive"))
    )
    (net (code "20") (name "FD_SIDESEL") (class "Default")
      (node (ref "CN4") (pin "32") (pinfunction "32_32") (pintype "passive"))
      (node (ref "IC9") (pin "8") (pinfunction "O_8") (pintype "open_collector"))
    )
    (net (code "21") (name "FD_STEP") (class "Default")
      (node (ref "CN4") (pin "20") (pinfunction "20_20") (pintype "passive"))
      (node (ref "IC9") (pin "2") (pinfunction "O_2") (pintype "open_collector"))
    )
    (net (code "22") (name "FD_STEPDIR") (class "Default")
      (node (ref "CN4") (pin "18") (pinfunction "18_18") (pintype "passive"))
      (node (ref "IC9") (pin "10") (pinfunction "O_10") (pintype "open_collector"))
    )
    (net (code "23") (name "FD_TRACK0") (class "Default")
      (node (ref "CN4") (pin "26") (pinfunction "26_26") (pintype "passive"))
      (node (ref "IC8") (pin "13") (pinfunction "I_13") (pintype "input"))
      (node (ref "RN1") (pin "5") (pinfunction "5_5") (pintype "passive"))
    )
    (net (code "24") (name "FD_WRDATA") (class "Default")
      (node (ref "CN4") (pin "22") (pinfunction "22_22") (pintype "passive"))
      (node (ref "IC9") (pin "4") (pinfunction "O_4") (pintype "open_collector"))
    )
    (net (code "25") (name "FD_WRGATE") (class "Default")
      (node (ref "CN4") (pin "24") (pinfunction "24_24") (pintype "passive"))
      (node (ref "IC9") (pin "6") (pinfunction "O_6") (pintype "open_collector"))
    )
    (net (code "26") (name "FD_WR_PROT") (class "Default")
      (node (ref "CN4") (pin "28") (pinfunction "28_28") (pintype "passive"))
      (node (ref "IC8") (pin "11") (pinfunction "I_11") (pintype "input"))
      (node (ref "RN1") (pin "4") (pinfunction "4_4") (pintype "passive"))
    )
    (net (code "27") (name "FI_DENSITY") (class "Default")
      (node (ref "IC5") (pin "90") (pinfunction "CLK5_90") (pintype "bidirectional"))
      (node (ref "IC8") (pin "2") (pinfunction "O_2") (pintype "output"))
    )
    (net (code "28") (name "FI_INDEX") (class "Default")
      (node (ref "IC5") (pin "88") (pinfunction "CLK7_88") (pintype "bidirectional"))
      (node (ref "IC8") (pin "4") (pinfunction "O_4") (pintype "output"))
    )
    (net (code "29") (name "FI_RDDAT") (class "Default")
      (node (ref "IC5") (pin "79") (pinfunction "IO79_79") (pintype "bidirectional"))
      (node (ref "IC8") (pin "8") (pinfunction "O_8") (pintype "output"))
    )
    (net (code "30") (name "FI_RY_CHG") (class "Default")
      (node (ref "IC5") (pin "86") (pinfunction "IO86_86") (pintype "bidirectional"))
      (node (ref "IC8") (pin "6") (pinfunction "O_6") (pintype "output"))
    )
    (net (code "31") (name "FI_TRACK0") (class "Default")
      (node (ref "IC5") (pin "89") (pinfunction "CLK6_89") (pintype "bidirectional"))
      (node (ref "IC8") (pin "12") (pinfunction "O_12") (pintype "output"))
    )
    (net (code "32") (name "FI_WRPROT") (class "Default")
      (node (ref "IC5") (pin "87") (pinfunction "IO87_87") (pintype "bidirectional"))
      (node (ref "IC8") (pin "10") (pinfunction "O_10") (pintype "output"))
    )
    (net (code "33") (name "FO_DENSITY") (class "Default")
      (node (ref "IC10") (pin "13") (pinfunction "I_13") (pintype "input"))
      (node (ref "IC5") (pin "114") (pinfunction "IO114_114") (pintype "bidirectional"))
    )
    (net (code "34") (name "FO_DS0") (class "Default")
      (node (ref "IC10") (pin "1") (pinfunction "I_1") (pintype "input"))
      (node (ref "IC5") (pin "115") (pinfunction "IO115_115") (pintype "bidirectional"))
    )
    (net (code "35") (name "FO_DS1") (class "Default")
      (node (ref "IC10") (pin "3") (pinfunction "I_3") (pintype "input"))
      (node (ref "IC5") (pin "113") (pinfunction "IO113_113") (pintype "bidirectional"))
    )
    (net (code "36") (name "FO_DS2") (class "Default")
      (node (ref "IC10") (pin "5") (pinfunction "I_5") (pintype "input"))
      (node (ref "IC5") (pin "104") (pinfunction "IO104_104") (pintype "bidirectional"))
    )
    (net (code "37") (name "FO_DS3") (class "Default")
      (node (ref "IC10") (pin "9") (pinfunction "I_9") (pintype "input"))
      (node (ref "IC5") (pin "103") (pinfunction "IO103_103") (pintype "bidirectional"))
    )
    (net (code "38") (name "FO_IN_USE") (class "Default")
      (node (ref "IC10") (pin "11") (pinfunction "I_11") (pintype "input"))
      (node (ref "IC5") (pin "112") (pinfunction "IO112_112") (pintype "bidirectional"))
    )
    (net (code "39") (name "FO_MOTEN") (class "Default")
      (node (ref "IC5") (pin "97") (pinfunction "IO97_97") (pintype "bidirectional"))
      (node (ref "IC9") (pin "13") (pinfunction "I_13") (pintype "input"))
    )
    (net (code "40") (name "FO_SIDESEL") (class "Default")
      (node (ref "IC5") (pin "92") (pinfunction "IO92_92") (pintype "bidirectional"))
      (node (ref "IC9") (pin "9") (pinfunction "I_9") (pintype "input"))
    )
    (net (code "41") (name "FO_STEP") (class "Default")
      (node (ref "IC5") (pin "99") (pinfunction "IO99_99") (pintype "bidirectional"))
      (node (ref "IC9") (pin "1") (pinfunction "I_1") (pintype "input"))
    )
    (net (code "42") (name "FO_STEPDIR") (class "Default")
      (node (ref "IC5") (pin "94") (pinfunction "IO94_94") (pintype "bidirectional"))
      (node (ref "IC9") (pin "11") (pinfunction "I_11") (pintype "input"))
    )
    (net (code "43") (name "FO_WRDATA") (class "Default")
      (node (ref "IC5") (pin "96") (pinfunction "IO96_96") (pintype "bidirectional"))
      (node (ref "IC9") (pin "3") (pinfunction "I_3") (pintype "input"))
    )
    (net (code "44") (name "FO_WRGATE") (class "Default")
      (node (ref "IC5") (pin "93") (pinfunction "IO93_93") (pintype "bidirectional"))
      (node (ref "IC9") (pin "5") (pinfunction "I_5") (pintype "input"))
    )
    (net (code "45") (name "FPGA20MHZ") (class "Default")
      (node (ref "IC5") (pin "17") (pinfunction "CLK0_17") (pintype "bidirectional"))
      (node (ref "XT2") (pin "3") (pinfunction "FO_3") (pintype "output"))
    )
    (net (code "46") (name "FPGALED") (class "Default")
      (node (ref "IC5") (pin "100") (pinfunction "IO100_100") (pintype "bidirectional"))
      (node (ref "LED3") (pin "C") (pinfunction "C_C") (pintype "passive"))
    )
    (net (code "47") (name "GND") (class "Default")
      (node (ref "C11") (pin "-") (pinfunction "-_-") (pintype "passive"))
      (node (ref "C12") (pin "2") (pinfunction "2_2") (pintype "passive"))
      (node (ref "C13") (pin "2") (pinfunction "2_2") (pintype "passive"))
      (node (ref "C14") (pin "-") (pinfunction "-_-") (pintype "passive"))
      (node (ref "C15") (pin "1") (pinfunction "1_1") (pintype "passive"))
      (node (ref "C16") (pin "2") (pinfunction "2_2") (pintype "passive"))
      (node (ref "C17") (pin "2") (pinfunction "2_2") (pintype "passive"))
      (node (ref "C18") (pin "2") (pinfunction "2_2") (pintype "passive"))
      (node (ref "C19") (pin "2") (pinfunction "2_2") (pintype "passive"))
      (node (ref "C2") (pin "2") (pinfunction "2_2") (pintype "passive"))
      (node (ref "C20") (pin "2") (pinfunction "2_2") (pintype "passive"))
      (node (ref "C21") (pin "2") (pinfunction "2_2") (pintype "passive"))
      (node (ref "C22") (pin "2") (pinfunction "2_2") (pintype "passive"))
      (node (ref "C23") (pin "2") (pinfunction "2_2") (pintype "passive"))
      (node (ref "C24") (pin "2") (pinfunction "2_2") (pintype "passive"))
      (node (ref "C25") (pin "2") (pinfunction "2_2") (pintype "passive"))
      (node (ref "C26") (pin "2") (pinfunction "2_2") (pintype "passive"))
      (node (ref "C27") (pin "2") (pinfunction "2_2") (pintype "passive"))
      (node (ref "C28") (pin "2") (pinfunction "2_2") (pintype "passive"))
      (node (ref "C29") (pin "1") (pinfunction "1_1") (pintype "passive"))
      (node (ref "C3") (pin "2") (pinfunction "2_2") (pintype "passive"))
      (node (ref "C30") (pin "1") (pinfunction "1_1") (pintype "passive"))
      (node (ref "C31") (pin "1") (pinfunction "1_1") (pintype "passive"))
      (node (ref "C32") (pin "1") (pinfunction "1_1") (pintype "passive"))
      (node (ref "C33") (pin "1") (pinfunction "1_1") (pintype "passive"))
      (node (ref "C34") (pin "1") (pinfunction "1_1") (pintype "passive"))
      (node (ref "C35") (pin "2") (pinfunction "2_2") (pintype "passive"))
      (node (ref "C36") (pin "2") (pinfunction "2_2") (pintype "passive"))
      (node (ref "C37") (pin "2") (pinfunction "2_2") (pintype "passive"))
      (node (ref "C38") (pin "2") (pinfunction "2_2") (pintype "passive"))
      (node (ref "C39") (pin "2") (pinfunction "2_2") (pintype "passive"))
      (node (ref "C4") (pin "-") (pinfunction "-_-") (pintype "passive"))
      (node (ref "C40") (pin "1") (pinfunction "1_1") (pintype "passive"))
      (node (ref "C41") (pin "1") (pinfunction "1_1") (pintype "passive"))
      (node (ref "C42") (pin "1") (pinfunction "1_1") (pintype "passive"))
      (node (ref "C43") (pin "1") (pinfunction "1_1") (pintype "passive"))
      (node (ref "C44") (pin "1") (pinfunction "1_1") (pintype "passive"))
      (node (ref "C45") (pin "2") (pinfunction "2_2") (pintype "passive"))
      (node (ref "C46") (pin "2") (pinfunction "2_2") (pintype "passive"))
      (node (ref "C47") (pin "2") (pinfunction "2_2") (pintype "passive"))
      (node (ref "C48") (pin "2") (pinfunction "2_2") (pintype "passive"))
      (node (ref "C49") (pin "2") (pinfunction "2_2") (pintype "passive"))
      (node (ref "C5") (pin "2") (pinfunction "2_2") (pintype "passive"))
      (node (ref "C50") (pin "2") (pinfunction "2_2") (pintype "passive"))
      (node (ref "C51") (pin "2") (pinfunction "2_2") (pintype "passive"))
      (node (ref "C52") (pin "2") (pinfunction "2_2") (pintype "passive"))
      (node (ref "C6") (pin "-") (pinfunction "-_-") (pintype "passive"))
      (node (ref "C7") (pin "2") (pinfunction "2_2") (pintype "passive"))
      (node (ref "C8") (pin "2") (pinfunction "2_2") (pintype "passive"))
      (node (ref "CN1") (pin "BARREL") (pinfunction "BAR_BARREL") (pintype "passive"))
      (node (ref "CN1") (pin "SW") (pinfunction "SW_SW") (pintype "passive"))
      (node (ref "CN2") (pin "4") (pinfunction "4_4") (pintype "passive"))
      (node (ref "CN2") (pin "S1") (pinfunction "S1_S1") (pintype "passive"))
      (node (ref "CN2") (pin "S2") (pinfunction "S2_S2") (pintype "passive"))
      (node (ref "CN3") (pin "3") (pinfunction "TGTVSS_3") (pintype "bidirectional"))
      (node (ref "CN4") (pin "1") (pinfunction "1_1") (pintype "passive"))
      (node (ref "CN4") (pin "11") (pinfunction "11_11") (pintype "passive"))
      (node (ref "CN4") (pin "13") (pinfunction "13_13") (pintype "passive"))
      (node (ref "CN4") (pin "15") (pinfunction "15_15") (pintype "passive"))
      (node (ref "CN4") (pin "17") (pinfunction "17_17") (pintype "passive"))
      (node (ref "CN4") (pin "19") (pinfunction "19_19") (pintype "passive"))
      (node (ref "CN4") (pin "21") (pinfunction "21_21") (pintype "passive"))
      (node (ref "CN4") (pin "23") (pinfunction "23_23") (pintype "passive"))
      (node (ref "CN4") (pin "25") (pinfunction "25_25") (pintype "passive"))
      (node (ref "CN4") (pin "27") (pinfunction "27_27") (pintype "passive"))
      (node (ref "CN4") (pin "29") (pinfunction "29_29") (pintype "passive"))
      (node (ref "CN4") (pin "3") (pinfunction "3_3") (pintype "passive"))
      (node (ref "CN4") (pin "31") (pinfunction "31_31") (pintype "passive"))
      (node (ref "CN4") (pin "33") (pinfunction "33_33") (pintype "passive"))
      (node (ref "CN4") (pin "35") (pinfunction "35_35") (pintype "passive"))
      (node (ref "CN4") (pin "5") (pinfunction "5_5") (pintype "passive"))
      (node (ref "CN4") (pin "7") (pinfunction "7_7") (pintype "passive"))
      (node (ref "CN4") (pin "9") (pinfunction "9_9") (pintype "passive"))
      (node (ref "CN5") (pin "1") (pinfunction "S_1") (pintype "passive"))
      (node (ref "CN5") (pin "3") (pinfunction "S_3") (pintype "passive"))
      (node (ref "D1") (pin "1") (pinfunction "A1_1") (pintype "passive"))
      (node (ref "D1") (pin "2") (pinfunction "A2_2") (pintype "passive"))
      (node (ref "D2") (pin "A") (pinfunction "A_A") (pintype "passive"))
      (node (ref "D3") (pin "A") (pinfunction "A_A") (pintype "passive"))
      (node (ref "D4") (pin "2") (pinfunction "A_2") (pintype "passive"))
      (node (ref "GND") (pin "TP") (pinfunction "TP_TP") (pintype "input"))
      (node (ref "IC1") (pin "4") (pinfunction "GND_4") (pintype "power_in"))
      (node (ref "IC1") (pin "PAD") (pinfunction "G_PAD") (pintype "input"))
      (node (ref "IC10") (pin "7") (pinfunction "GND_7") (pintype "power_in"))
      (node (ref "IC2") (pin "15") (pinfunction "DGND_15") (pintype "power_in"))
      (node (ref "IC2") (pin "18") (pinfunction "AGND_18") (pintype "power_in"))
      (node (ref "IC2") (pin "2") (pinfunction "FB3_2") (pintype "input"))
      (node (ref "IC2") (pin "20") (pinfunction "IN3_20") (pintype "input"))
      (node (ref "IC2") (pin "3") (pinfunction "EN3_3") (pintype "input"))
      (node (ref "IC2") (pin "6") (pinfunction "DGND_6") (pintype "power_in"))
      (node (ref "IC2") (pin "E@1") (pinfunction "DGND_E@1") (pintype "power_in"))
      (node (ref "IC2") (pin "E@2") (pinfunction "DGND_E@2") (pintype "power_in"))
      (node (ref "IC2") (pin "E@3") (pinfunction "DGND_E@3") (pintype "power_in"))
      (node (ref "IC2") (pin "E@4") (pinfunction "DGND_E@4") (pintype "power_in"))
      (node (ref "IC3") (pin "11") (pinfunction "VSS_11") (pintype "power_in"))
      (node (ref "IC3") (pin "26") (pinfunction "AVSS_26") (pintype "bidirectional"))
      (node (ref "IC3") (pin "31") (pinfunction "VSS_31") (pintype "power_in"))
      (node (ref "IC3") (pin "51") (pinfunction "VSS_51") (pintype "power_in"))
      (node (ref "IC3") (pin "70") (pinfunction "VSS_70") (pintype "power_in"))
      (node (ref "IC4") (pin "2") (pinfunction "GND_2") (pintype "power_in"))
      (node (ref "IC4") (pin "5") (pinfunction "GND_5") (pintype "power_in"))
      (node (ref "IC5") (pin "105") (pinfunction "GND_105") (pintype "power_in"))
      (node (ref "IC5") (pin "106") (pinfunction "GND_106") (pintype "power_in"))
      (node (ref "IC5") (pin "108") (pinfunction "GND_108") (pintype "power_in"))
      (node (ref "IC5") (pin "110") (pinfunction "GND_110") (pintype "power_in"))
      (node (ref "IC5") (pin "111") (pinfunction "GND_111") (pintype "power_in"))
      (node (ref "IC5") (pin "117") (pinfunction "GND_117") (pintype "power_in"))
      (node (ref "IC5") (pin "123") (pinfunction "GND_123") (pintype "power_in"))
      (node (ref "IC5") (pin "128") (pinfunction "GND_128") (pintype "power_in"))
      (node (ref "IC5") (pin "130") (pinfunction "GND_130") (pintype "power_in"))
      (node (ref "IC5") (pin "140") (pinfunction "GND_140") (pintype "power_in"))
      (node (ref "IC5") (pin "16") (pinfunction "NCE_16") (pintype "input"))
      (node (ref "IC5") (pin "19") (pinfunction "GND_19") (pintype "power_in"))
      (node (ref "IC5") (pin "27") (pinfunction "GND_27") (pintype "power_in"))
      (node (ref "IC5") (pin "33") (pinfunction "GND_33") (pintype "power_in"))
      (node (ref "IC5") (pin "34") (pinfunction "GND_34") (pintype "power_in"))
      (node (ref "IC5") (pin "36") (pinfunction "GND_36") (pintype "power_in"))
      (node (ref "IC5") (pin "38") (pinfunction "GND_38") (pintype "power_in"))
      (node (ref "IC5") (pin "39") (pinfunction "GND_39") (pintype "power_in"))
      (node (ref "IC5") (pin "49") (pinfunction "GND_49") (pintype "power_in"))
      (node (ref "IC5") (pin "56") (pinfunction "GND_56") (pintype "power_in"))
      (node (ref "IC5") (pin "6") (pinfunction "GND_6") (pintype "power_in"))
      (node (ref "IC5") (pin "61") (pinfunction "GND_61") (pintype "power_in"))
      (node (ref "IC5") (pin "68") (pinfunction "GND_68") (pintype "power_in"))
      (node (ref "IC5") (pin "78") (pinfunction "GND_78") (pintype "power_in"))
      (node (ref "IC5") (pin "80") (pinfunction "GND_80") (pintype "power_in"))
      (node (ref "IC5") (pin "84") (pinfunction "MSEL1_84") (pintype "input"))
      (node (ref "IC5") (pin "98") (pinfunction "GND_98") (pintype "power_in"))
      (node (ref "IC6") (pin "12") (pinfunction "GND_12") (pintype "power_in"))
      (node (ref "IC6") (pin "34") (pinfunction "GND_34") (pintype "power_in"))
      (node (ref "IC7") (pin "7") (pinfunction "GND_7") (pintype "power_in"))
      (node (ref "IC8") (pin "7") (pinfunction "GND_7") (pintype "power_in"))
      (node (ref "IC9") (pin "7") (pinfunction "GND_7") (pintype "power_in"))
      (node (ref "JP1") (pin "1") (pinfunction "1_1") (pintype "passive"))
      (node (ref "JP2") (pin "1") (pinfunction "1_1") (pintype "passive"))
      (node (ref "LED1") (pin "C") (pinfunction "C_C") (pintype "passive"))
      (node (ref "R1") (pin "1") (pinfunction "1_1") (pintype "passive"))
      (node (ref "R10") (pin "1") (pinfunction "1_1") (pintype "passive"))
      (node (ref "R4") (pin "1") (pinfunction "1_1") (pintype "passive"))
      (node (ref "R8") (pin "1") (pinfunction "1_1") (pintype "passive"))
      (node (ref "XT2") (pin "2") (pinfunction "GND_2") (pintype "power_in"))
    )
    (net (code "48") (name "HSB1_3V") (class "Default")
      (node (ref "IC5") (pin "76") (pinfunction "IO76_76") (pintype "bidirectional"))
      (node (ref "IC7") (pin "2") (pinfunction "A1_2") (pintype "bidirectional"))
    )
    (net (code "49") (name "HSB1_5V") (class "Default")
      (node (ref "CN4") (pin "37") (pinfunction "37_37") (pintype "passive"))
      (node (ref "IC7") (pin "13") (pinfunction "B1_13") (pintype "bidirectional"))
    )
    (net (code "50") (name "HSB2_3V") (class "Default")
      (node (ref "IC5") (pin "75") (pinfunction "IO75_75") (pintype "bidirectional"))
      (node (ref "IC7") (pin "3") (pinfunction "A2_3") (pintype "bidirectional"))
    )
    (net (code "51") (name "HSB2_5V") (class "Default")
      (node (ref "CN4") (pin "38") (pinfunction "38_38") (pintype "passive"))
      (node (ref "IC7") (pin "12") (pinfunction "B2_12") (pintype "bidirectional"))
    )
    (net (code "52") (name "HSB3_3V") (class "Default")
      (node (ref "IC5") (pin "74") (pinfunction "IO74_74") (pintype "bidirectional"))
      (node (ref "IC7") (pin "4") (pinfunction "A3_4") (pintype "bidirectional"))
    )
    (net (code "53") (name "HSB3_5V") (class "Default")
      (node (ref "CN4") (pin "39") (pinfunction "39_39") (pintype "passive"))
      (node (ref "IC7") (pin "11") (pinfunction "B3_11") (pintype "bidirectional"))
    )
    (net (code "54") (name "HSB4_3V") (class "Default")
      (node (ref "IC5") (pin "73") (pinfunction "IO73_73") (pintype "bidirectional"))
      (node (ref "IC7") (pin "5") (pinfunction "A4_5") (pintype "bidirectional"))
    )
    (net (code "55") (name "HSB4_5V") (class "Default")
      (node (ref "CN4") (pin "40") (pinfunction "40_40") (pintype "passive"))
      (node (ref "IC7") (pin "10") (pinfunction "B4_10") (pintype "bidirectional"))
    )
    (net (code "56") (name "ICSP_MCLR") (class "Default")
      (node (ref "CN3") (pin "1") (pinfunction "MCLR_1") (pintype "bidirectional"))
      (node (ref "IC3") (pin "9") (pinfunction "~{MCLR}_9") (pintype "input"))
      (node (ref "R9") (pin "2") (pinfunction "2_2") (pintype "passive"))
    )
    (net (code "57") (name "ICSP_RB6_PGC") (class "Default")
      (node (ref "CN3") (pin "5") (pinfunction "PGC_5") (pintype "bidirectional"))
      (node (ref "IC3") (pin "52") (pinfunction "RB6/KBI2/PGC_52") (pintype "bidirectional"))
    )
    (net (code "58") (name "ICSP_RB7_PGD") (class "Default")
      (node (ref "CN3") (pin "4") (pinfunction "PGD_4") (pintype "bidirectional"))
      (node (ref "IC3") (pin "47") (pinfunction "RB7/KBI3/PGD_47") (pintype "bidirectional"))
    )
    (net (code "59") (name "MCULED") (class "Default")
      (node (ref "IC3") (pin "41") (pinfunction "RJ6/~{LB}_41") (pintype "bidirectional"))
      (node (ref "LED2") (pin "C") (pinfunction "C_C") (pintype "passive"))
    )
    (net (code "60") (name "Net-(D1-C)") (class "Default")
      (node (ref "C1") (pin "2") (pinfunction "2_2") (pintype "passive"))
      (node (ref "D1") (pin "K") (pinfunction "C_K") (pintype "passive"))
      (node (ref "IC1") (pin "1") (pinfunction "OUTPUT_1") (pintype "output"))
      (node (ref "L1") (pin "1") (pinfunction "1_1") (pintype "passive"))
    )
    (net (code "61") (name "Net-(D4-C)") (class "Default")
      (node (ref "D4") (pin "1") (pinfunction "C_1") (pintype "passive"))
      (node (ref "L3") (pin "1") (pinfunction "1_1") (pintype "passive"))
      (node (ref "Q3") (pin "3") (pinfunction "D_3") (pintype "passive"))
    )
    (net (code "62") (name "Net-(IC1-CB)") (class "Default")
      (node (ref "C1") (pin "1") (pinfunction "1_1") (pintype "passive"))
      (node (ref "IC1") (pin "3") (pinfunction "CB_3") (pintype "bidirectional"))
    )
    (net (code "63") (name "Net-(IC1-FB)") (class "Default")
      (node (ref "IC1") (pin "6") (pinfunction "FB_6") (pintype "input"))
      (node (ref "R1") (pin "2") (pinfunction "2_2") (pintype "passive"))
      (node (ref "R2") (pin "1") (pinfunction "1_1") (pintype "passive"))
    )
    (net (code "64") (name "Net-(IC1-IADJ)") (class "Default")
      (node (ref "IC1") (pin "5") (pinfunction "IADJ_5") (pintype "bidirectional"))
      (node (ref "R4") (pin "2") (pinfunction "2_2") (pintype "passive"))
    )
    (net (code "65") (name "Net-(IC1-SS)") (class "Default")
      (node (ref "C5") (pin "1") (pinfunction "1_1") (pintype "passive"))
      (node (ref "IC1") (pin "7") (pinfunction "SS_7") (pintype "bidirectional"))
    )
    (net (code "66") (name "Net-(IC2-FB2)") (class "Default")
      (node (ref "IC2") (pin "10") (pinfunction "FB2_10") (pintype "input"))
      (node (ref "R7") (pin "1") (pinfunction "1_1") (pintype "passive"))
      (node (ref "R8") (pin "2") (pinfunction "2_2") (pintype "passive"))
    )
    (net (code "67") (name "Net-(IC2-IS1)") (class "Default")
      (node (ref "C10") (pin "2") (pinfunction "2_2") (pintype "passive"))
      (node (ref "IC2") (pin "12") (pinfunction "IS1_12") (pintype "input"))
      (node (ref "Q2") (pin "2") (pinfunction "S_2") (pintype "passive"))
      (node (ref "R6") (pin "1") (pinfunction "1_1") (pintype "passive"))
    )
    (net (code "68") (name "Net-(IC2-IS2)") (class "Default")
      (node (ref "C9") (pin "2") (pinfunction "2_2") (pintype "passive"))
      (node (ref "IC2") (pin "9") (pinfunction "IS2_9") (pintype "input"))
      (node (ref "Q3") (pin "2") (pinfunction "S_2") (pintype "passive"))
      (node (ref "R5") (pin "1") (pinfunction "1_1") (pintype "passive"))
    )
    (net (code "69") (name "Net-(IC2-SS1)") (class "Default")
      (node (ref "C12") (pin "1") (pinfunction "1_1") (pintype "passive"))
      (node (ref "IC2") (pin "16") (pinfunction "SS1_16") (pintype "input"))
    )
    (net (code "70") (name "Net-(IC2-SS2)") (class "Default")
      (node (ref "C13") (pin "1") (pinfunction "1_1") (pintype "passive"))
      (node (ref "IC2") (pin "5") (pinfunction "SS2_5") (pintype "input"))
    )
    (net (code "71") (name "Net-(IC2-SW1)") (class "Default")
      (node (ref "IC2") (pin "14") (pinfunction "SW1_14") (pintype "input"))
      (node (ref "Q2") (pin "1") (pinfunction "G_1") (pintype "passive"))
    )
    (net (code "72") (name "Net-(IC2-SW2)") (class "Default")
      (node (ref "IC2") (pin "7") (pinfunction "SW2_7") (pintype "input"))
      (node (ref "Q3") (pin "1") (pinfunction "G_1") (pintype "passive"))
    )
    (net (code "73") (name "Net-(IC3-RC6{slash}TX1{slash}CK1)") (class "Default")
      (node (ref "IC3") (pin "37") (pinfunction "RC6/TX1/CK1_37") (pintype "bidirectional"))
      (node (ref "JP2") (pin "2") (pinfunction "2_2") (pintype "passive"))
    )
    (net (code "74") (name "Net-(IC3-RC7{slash}RX1{slash}DT1)") (class "Default")
      (node (ref "IC3") (pin "38") (pinfunction "RC7/RX1/DT1_38") (pintype "bidirectional"))
      (node (ref "JP2") (pin "3") (pinfunction "3_3") (pintype "passive"))
    )
    (net (code "75") (name "Net-(IC3-RJ5{slash}~{CE})") (class "Default")
      (node (ref "IC3") (pin "40") (pinfunction "RJ5/~{CE}_40") (pintype "bidirectional"))
      (node (ref "JP1") (pin "2") (pinfunction "2_2") (pintype "passive"))
      (node (ref "R13") (pin "1") (pinfunction "1_1") (pintype "passive"))
    )
    (net (code "76") (name "Net-(IC3-VDDCORE{slash}VCAP)") (class "Default")
      (node (ref "C15") (pin "2") (pinfunction "2_2") (pintype "passive"))
      (node (ref "IC3") (pin "12") (pinfunction "VDDCORE/VCAP_12") (pintype "bidirectional"))
    )
    (net (code "77") (name "Net-(LED1-PadA)") (class "Default")
      (node (ref "LED1") (pin "A") (pinfunction "A_A") (pintype "passive"))
      (node (ref "R14") (pin "1") (pinfunction "1_1") (pintype "passive"))
    )
    (net (code "78") (name "Net-(LED2-PadA)") (class "Default")
      (node (ref "LED2") (pin "A") (pinfunction "A_A") (pintype "passive"))
      (node (ref "R15") (pin "1") (pinfunction "1_1") (pintype "passive"))
    )
    (net (code "79") (name "Net-(LED3-PadA)") (class "Default")
      (node (ref "LED3") (pin "A") (pinfunction "A_A") (pintype "passive"))
      (node (ref "R16") (pin "1") (pinfunction "1_1") (pintype "passive"))
    )
    (net (code "80") (name "Net-(Q1-D1)") (class "Default")
      (node (ref "CN1") (pin "PIN") (pinfunction "PIN_PIN") (pintype "passive"))
      (node (ref "Q1") (pin "1") (pinfunction "D1_1") (pintype "passive"))
      (node (ref "Q1") (pin "2") (pinfunction "D2_2") (pintype "passive"))
      (node (ref "Q1") (pin "5") (pinfunction "D3_5") (pintype "passive"))
      (node (ref "Q1") (pin "6") (pinfunction "D4_6") (pintype "passive"))
    )
    (net (code "81") (name "Net-(Q1-G)") (class "Default")
      (node (ref "D2") (pin "C") (pinfunction "C_C") (pintype "passive"))
      (node (ref "Q1") (pin "3") (pinfunction "G_3") (pintype "passive"))
      (node (ref "R3") (pin "1") (pinfunction "1_1") (pintype "passive"))
    )
    (net (code "82") (name "Net-(Q2-D)") (class "Default")
      (node (ref "D3") (pin "C") (pinfunction "C_C") (pintype "passive"))
      (node (ref "L2") (pin "1") (pinfunction "1_1") (pintype "passive"))
      (node (ref "Q2") (pin "3") (pinfunction "D_3") (pintype "passive"))
    )
    (net (code "83") (name "PIC_CLKI") (class "Default")
      (node (ref "C21") (pin "1") (pinfunction "1_1") (pintype "passive"))
      (node (ref "IC3") (pin "49") (pinfunction "OSC1/CLKI/RA7_49") (pintype "bidirectional"))
      (node (ref "XT1") (pin "2") (pinfunction "2_2") (pintype "passive"))
    )
    (net (code "84") (name "PIC_CLKO") (class "Default")
      (node (ref "C20") (pin "1") (pinfunction "1_1") (pintype "passive"))
      (node (ref "IC3") (pin "50") (pinfunction "OSC2/CLKO/RA6_50") (pintype "bidirectional"))
      (node (ref "XT1") (pin "1") (pinfunction "1_1") (pintype "passive"))
    )
    (net (code "85") (name "PMALH") (class "Default")
      (node (ref "IC3") (pin "54") (pinfunction "RB4/KBI0/PMA1_54") (pintype "bidirectional"))
      (node (ref "IC5") (pin "71") (pinfunction "IO71_71") (pintype "bidirectional"))
    )
    (net (code "86") (name "PMALL") (class "Default")
      (node (ref "IC3") (pin "53") (pinfunction "RB5/KBI1/PMA0_53") (pintype "bidirectional"))
      (node (ref "IC5") (pin "72") (pinfunction "IO72_72") (pintype "bidirectional"))
    )
    (net (code "87") (name "PMD0") (class "Default")
      (node (ref "IC3") (pin "72") (pinfunction "RD0/AD0/PMD0_72") (pintype "bidirectional"))
      (node (ref "IC5") (pin "48") (pinfunction "IO48_48") (pintype "bidirectional"))
    )
    (net (code "88") (name "PMD1") (class "Default")
      (node (ref "IC3") (pin "69") (pinfunction "RD1/AD1/PMD1_69") (pintype "bidirectional"))
      (node (ref "IC5") (pin "53") (pinfunction "IO53_53") (pintype "bidirectional"))
    )
    (net (code "89") (name "PMD2") (class "Default")
      (node (ref "IC3") (pin "68") (pinfunction "RD2/AD2/PMD2_68") (pintype "bidirectional"))
      (node (ref "IC5") (pin "55") (pinfunction "IO55_55") (pintype "bidirectional"))
    )
    (net (code "90") (name "PMD3") (class "Default")
      (node (ref "IC3") (pin "67") (pinfunction "RD3/AD3/PMD3_67") (pintype "bidirectional"))
      (node (ref "IC5") (pin "57") (pinfunction "IO57_57") (pintype "bidirectional"))
    )
    (net (code "91") (name "PMD4") (class "Default")
      (node (ref "IC3") (pin "66") (pinfunction "RD4/AD4/PMD4/SDO2_66") (pintype "bidirectional"))
      (node (ref "IC5") (pin "58") (pinfunction "IO58_58") (pintype "bidirectional"))
    )
    (net (code "92") (name "PMD5") (class "Default")
      (node (ref "IC3") (pin "65") (pinfunction "RD5/AD5/PMD5/SDI2/SDA2_65") (pintype "bidirectional"))
      (node (ref "IC5") (pin "59") (pinfunction "IO59_59") (pintype "bidirectional"))
    )
    (net (code "93") (name "PMD6") (class "Default")
      (node (ref "IC3") (pin "64") (pinfunction "RD6/AD6/PMD6/SCK2/SCL2_64") (pintype "bidirectional"))
      (node (ref "IC5") (pin "60") (pinfunction "IO60_60") (pintype "bidirectional"))
    )
    (net (code "94") (name "PMD7") (class "Default")
      (node (ref "IC3") (pin "63") (pinfunction "RD7/AD7/PMD7/~{SS2}_63") (pintype "bidirectional"))
      (node (ref "IC5") (pin "63") (pinfunction "IO63_63") (pintype "bidirectional"))
    )
    (net (code "95") (name "PMRD") (class "Default")
      (node (ref "IC3") (pin "4") (pinfunction "RE0/AD8/PMRD/P2D_4") (pintype "bidirectional"))
      (node (ref "IC5") (pin "40") (pinfunction "IO40_40") (pintype "bidirectional"))
    )
    (net (code "96") (name "PMWR") (class "Default")
      (node (ref "IC3") (pin "3") (pinfunction "RE1/AD9/PMWR/P2C_3") (pintype "bidirectional"))
      (node (ref "IC5") (pin "41") (pinfunction "IO41_41") (pintype "bidirectional"))
    )
    (net (code "97") (name "SRAM_A0") (class "Default")
      (node (ref "IC5") (pin "32") (pinfunction "IO32_32") (pintype "bidirectional"))
      (node (ref "IC6") (pin "3") (pinfunction "A0_3") (pintype "input"))
    )
    (net (code "98") (name "SRAM_A1") (class "Default")
      (node (ref "IC5") (pin "31") (pinfunction "IO31_31") (pintype "bidirectional"))
      (node (ref "IC6") (pin "4") (pinfunction "A1_4") (pintype "input"))
    )
    (net (code "99") (name "SRAM_A2") (class "Default")
      (node (ref "IC5") (pin "30") (pinfunction "IO30_30") (pintype "bidirectional"))
      (node (ref "IC6") (pin "5") (pinfunction "A2_5") (pintype "input"))
    )
    (net (code "100") (name "SRAM_A3") (class "Default")
      (node (ref "IC5") (pin "28") (pinfunction "IO28_28") (pintype "bidirectional"))
      (node (ref "IC6") (pin "6") (pinfunction "A3_6") (pintype "input"))
    )
    (net (code "101") (name "SRAM_A4") (class "Default")
      (node (ref "IC5") (pin "25") (pinfunction "IO25_25") (pintype "bidirectional"))
      (node (ref "IC6") (pin "7") (pinfunction "A4_7") (pintype "input"))
    )
    (net (code "102") (name "SRAM_A5") (class "Default")
      (node (ref "IC5") (pin "2") (pinfunction "IO2_2") (pintype "output"))
      (node (ref "IC6") (pin "16") (pinfunction "A5_16") (pintype "input"))
    )
    (net (code "103") (name "SRAM_A6") (class "Default")
      (node (ref "IC5") (pin "1") (pinfunction "IO1_1") (pintype "output"))
      (node (ref "IC6") (pin "17") (pinfunction "A6_17") (pintype "input"))
    )
    (net (code "104") (name "SRAM_A7") (class "Default")
      (node (ref "IC5") (pin "144") (pinfunction "IO144_144") (pintype "bidirectional"))
      (node (ref "IC6") (pin "18") (pinfunction "A7_18") (pintype "input"))
    )
    (net (code "105") (name "SRAM_A8") (class "Default")
      (node (ref "IC5") (pin "143") (pinfunction "IO143_143") (pintype "bidirectional"))
      (node (ref "IC6") (pin "19") (pinfunction "A8_19") (pintype "input"))
    )
    (net (code "106") (name "SRAM_A9") (class "Default")
      (node (ref "IC5") (pin "142") (pinfunction "IO142_142") (pintype "bidirectional"))
      (node (ref "IC6") (pin "20") (pinfunction "A9_20") (pintype "input"))
    )
    (net (code "107") (name "SRAM_A10") (class "Default")
      (node (ref "IC5") (pin "118") (pinfunction "IO118_118") (pintype "bidirectional"))
      (node (ref "IC6") (pin "26") (pinfunction "A10_26") (pintype "input"))
    )
    (net (code "108") (name "SRAM_A11") (class "Default")
      (node (ref "IC5") (pin "121") (pinfunction "IO121_121") (pintype "bidirectional"))
      (node (ref "IC6") (pin "27") (pinfunction "A11_27") (pintype "input"))
    )
    (net (code "109") (name "SRAM_A12") (class "Default")
      (node (ref "IC5") (pin "122") (pinfunction "IO122_122") (pintype "bidirectional"))
      (node (ref "IC6") (pin "28") (pinfunction "A12_28") (pintype "input"))
    )
    (net (code "110") (name "SRAM_A13") (class "Default")
      (node (ref "IC5") (pin "125") (pinfunction "IO125_125") (pintype "bidirectional"))
      (node (ref "IC6") (pin "29") (pinfunction "A13_29") (pintype "input"))
    )
    (net (code "111") (name "SRAM_A14") (class "Default")
      (node (ref "IC5") (pin "126") (pinfunction "IO126_126") (pintype "bidirectional"))
      (node (ref "IC6") (pin "30") (pinfunction "A14_30") (pintype "input"))
    )
    (net (code "112") (name "SRAM_A15") (class "Default")
      (node (ref "IC5") (pin "136") (pinfunction "IO136_136") (pintype "bidirectional"))
      (node (ref "IC6") (pin "38") (pinfunction "A15_38") (pintype "input"))
    )
    (net (code "113") (name "SRAM_A16") (class "Default")
      (node (ref "IC5") (pin "137") (pinfunction "IO137_137") (pintype "bidirectional"))
      (node (ref "IC6") (pin "39") (pinfunction "A16_39") (pintype "input"))
    )
    (net (code "114") (name "SRAM_A17") (class "Default")
      (node (ref "IC5") (pin "139") (pinfunction "IO139_139") (pintype "bidirectional"))
      (node (ref "IC6") (pin "40") (pinfunction "A17_40") (pintype "input"))
    )
    (net (code "115") (name "SRAM_A18") (class "Default")
      (node (ref "IC5") (pin "141") (pinfunction "IO141_141") (pintype "bidirectional"))
      (node (ref "IC6") (pin "41") (pinfunction "A18_41") (pintype "input"))
    )
    (net (code "116") (name "SRAM_CE") (class "Default")
      (node (ref "IC5") (pin "24") (pinfunction "IO24_24") (pintype "bidirectional"))
      (node (ref "IC6") (pin "8") (pinfunction "CE_8") (pintype "input"))
    )
    (net (code "117") (name "SRAM_D0") (class "Default")
      (node (ref "IC5") (pin "9") (pinfunction "IO9_9") (pintype "bidirectional"))
      (node (ref "IC6") (pin "9") (pinfunction "I/O00_9") (pintype "bidirectional"))
    )
    (net (code "118") (name "SRAM_D1") (class "Default")
      (node (ref "IC5") (pin "8") (pinfunction "IO8_8") (pintype "bidirectional"))
      (node (ref "IC6") (pin "10") (pinfunction "I/O01_10") (pintype "bidirectional"))
    )
    (net (code "119") (name "SRAM_D2") (class "Default")
      (node (ref "IC5") (pin "7") (pinfunction "IO7_7") (pintype "bidirectional"))
      (node (ref "IC6") (pin "13") (pinfunction "I/O02_13") (pintype "bidirectional"))
    )
    (net (code "120") (name "SRAM_D3") (class "Default")
      (node (ref "IC5") (pin "4") (pinfunction "IO4_4") (pintype "bidirectional"))
      (node (ref "IC6") (pin "14") (pinfunction "I/O03_14") (pintype "bidirectional"))
    )
    (net (code "121") (name "SRAM_D4") (class "Default")
      (node (ref "IC5") (pin "129") (pinfunction "IO129_129") (pintype "bidirectional"))
      (node (ref "IC6") (pin "31") (pinfunction "I/O04_31") (pintype "bidirectional"))
    )
    (net (code "122") (name "SRAM_D5") (class "Default")
      (node (ref "IC5") (pin "132") (pinfunction "IO132_132") (pintype "bidirectional"))
      (node (ref "IC6") (pin "32") (pinfunction "I/O05_32") (pintype "bidirectional"))
    )
    (net (code "123") (name "SRAM_D6") (class "Default")
      (node (ref "IC5") (pin "133") (pinfunction "IO133_133") (pintype "bidirectional"))
      (node (ref "IC6") (pin "35") (pinfunction "I/O06_35") (pintype "bidirectional"))
    )
    (net (code "124") (name "SRAM_D7") (class "Default")
      (node (ref "IC5") (pin "134") (pinfunction "IO134_134") (pintype "bidirectional"))
      (node (ref "IC6") (pin "36") (pinfunction "I/O07_36") (pintype "bidirectional"))
    )
    (net (code "125") (name "SRAM_OE") (class "Default")
      (node (ref "IC5") (pin "135") (pinfunction "IO135_135") (pintype "bidirectional"))
      (node (ref "IC6") (pin "37") (pinfunction "OE_37") (pintype "input"))
    )
    (net (code "126") (name "SRAM_WE") (class "Default")
      (node (ref "IC5") (pin "3") (pinfunction "IO3_3") (pintype "bidirectional"))
      (node (ref "IC6") (pin "15") (pinfunction "WE_15") (pintype "input"))
    )
    (net (code "127") (name "TCK") (class "Default")
      (node (ref "IC5") (pin "12") (pinfunction "TCK_12") (pintype "input"))
      (node (ref "TCK") (pin "TP") (pinfunction "TP_TP") (pintype "input"))
    )
    (net (code "128") (name "TDI") (class "Default")
      (node (ref "IC5") (pin "13") (pinfunction "TDI_13") (pintype "input"))
      (node (ref "TDI") (pin "TP") (pinfunction "TP_TP") (pintype "input"))
    )
    (net (code "129") (name "TDO") (class "Default")
      (node (ref "IC5") (pin "10") (pinfunction "TDO_10") (pintype "output"))
      (node (ref "TDO") (pin "TP") (pinfunction "TP_TP") (pintype "input"))
    )
    (net (code "130") (name "TMS") (class "Default")
      (node (ref "IC5") (pin "11") (pinfunction "TMS_11") (pintype "input"))
      (node (ref "TMS") (pin "TP") (pinfunction "TP_TP") (pintype "input"))
    )
    (net (code "131") (name "USBD+") (class "Default")
      (node (ref "CN2") (pin "3") (pinfunction "3_3") (pintype "passive"))
      (node (ref "IC3") (pin "16") (pinfunction "RF4/D+_16") (pintype "bidirectional"))
      (node (ref "IC4") (pin "4") (pinfunction "B_4") (pintype "bidirectional"))
    )
    (net (code "132") (name "USBD-") (class "Default")
      (node (ref "CN2") (pin "2") (pinfunction "2_2") (pintype "passive"))
      (node (ref "IC3") (pin "17") (pinfunction "RF3/D-_17") (pintype "bidirectional"))
      (node (ref "IC4") (pin "6") (pinfunction "A_6") (pintype "bidirectional"))
    )
    (net (code "133") (name "USBDETECT") (class "Default")
      (node (ref "CN2") (pin "1") (pinfunction "1_1") (pintype "passive"))
      (node (ref "IC3") (pin "18") (pinfunction "RF2/PMA5/AN7/C2INB_18") (pintype "bidirectional"))
      (node (ref "R10") (pin "2") (pinfunction "2_2") (pintype "passive"))
    )
    (net (code "134") (name "unconnected-(CN3-AUX-Pad6)") (class "Default")
      (node (ref "CN3") (pin "6") (pinfunction "AUX_6") (pintype "bidirectional"))
    )
    (net (code "135") (name "unconnected-(IC2-OUT3-Pad1)") (class "Default")
      (node (ref "IC2") (pin "1") (pinfunction "OUT3_1") (pintype "output"))
    )
    (net (code "136") (name "unconnected-(IC2-SS3-Pad19)") (class "Default")
      (node (ref "IC2") (pin "19") (pinfunction "SS3_19") (pintype "input"))
    )
    (net (code "137") (name "unconnected-(IC3-RA0{slash}AN0-Pad30)") (class "Default")
      (node (ref "IC3") (pin "30") (pinfunction "RA0/AN0_30") (pintype "bidirectional"))
    )
    (net (code "138") (name "unconnected-(IC3-RA1{slash}AN1-Pad29)") (class "Default")
      (node (ref "IC3") (pin "29") (pinfunction "RA1/AN1_29") (pintype "bidirectional"))
    )
    (net (code "139") (name "unconnected-(IC3-RA2{slash}AN2{slash}VREF--Pad28)") (class "Default")
      (node (ref "IC3") (pin "28") (pinfunction "RA2/AN2/VREF-_28") (pintype "bidirectional"))
    )
    (net (code "140") (name "unconnected-(IC3-RA3{slash}AN3{slash}VREF+-Pad27)") (class "Default")
      (node (ref "IC3") (pin "27") (pinfunction "RA3/AN3/VREF+_27") (pintype "bidirectional"))
    )
    (net (code "141") (name "unconnected-(IC3-RA4{slash}PMD5{slash}T0CKI-Pad34)") (class "Default")
      (node (ref "IC3") (pin "34") (pinfunction "RA4/PMD5/T0CKI_34") (pintype "bidirectional"))
    )
    (net (code "142") (name "unconnected-(IC3-RA5{slash}PMD4{slash}AN4{slash}C2INA-Pad33)") (class "Default")
      (node (ref "IC3") (pin "33") (pinfunction "RA5/PMD4/AN4/C2INA_33") (pintype "bidirectional"))
    )
    (net (code "143") (name "unconnected-(IC3-RB0{slash}FLT0{slash}INT0-Pad58)") (class "Default")
      (node (ref "IC3") (pin "58") (pinfunction "RB0/FLT0/INT0_58") (pintype "bidirectional"))
    )
    (net (code "144") (name "unconnected-(IC3-RB1{slash}INT1{slash}PMA4-Pad57)") (class "Default")
      (node (ref "IC3") (pin "57") (pinfunction "RB1/INT1/PMA4_57") (pintype "bidirectional"))
    )
    (net (code "145") (name "unconnected-(IC3-RB2{slash}INT2{slash}PMA3-Pad56)") (class "Default")
      (node (ref "IC3") (pin "56") (pinfunction "RB2/INT2/PMA3_56") (pintype "bidirectional"))
    )
    (net (code "146") (name "unconnected-(IC3-RB3{slash}INT3{slash}ECCP2{slash}P2A{slash}PMA2-Pad55)") (class "Default")
      (node (ref "IC3") (pin "55") (pinfunction "RB3/INT3/ECCP2/P2A/PMA2_55") (pintype "bidirectional"))
    )
    (net (code "147") (name "unconnected-(IC3-RC0{slash}T1OSO{slash}T13CKI-Pad36)") (class "Default")
      (node (ref "IC3") (pin "36") (pinfunction "RC0/T1OSO/T13CKI_36") (pintype "bidirectional"))
    )
    (net (code "148") (name "unconnected-(IC3-RC1{slash}T1OSI{slash}ECCP2{slash}P2A-Pad35)") (class "Default")
      (node (ref "IC3") (pin "35") (pinfunction "RC1/T1OSI/ECCP2/P2A_35") (pintype "bidirectional"))
    )
    (net (code "149") (name "unconnected-(IC3-RC2{slash}ECCP1{slash}P1A-Pad43)") (class "Default")
      (node (ref "IC3") (pin "43") (pinfunction "RC2/ECCP1/P1A_43") (pintype "bidirectional"))
    )
    (net (code "150") (name "unconnected-(IC3-RE2{slash}AD10{slash}PMBE{slash}P2B-Pad78)") (class "Default")
      (node (ref "IC3") (pin "78") (pinfunction "RE2/AD10/PMBE/P2B_78") (pintype "bidirectional"))
    )
    (net (code "151") (name "unconnected-(IC3-RE3{slash}AD11{slash}PMA13{slash}P3C{slash}REFO-Pad77)") (class "Default")
      (node (ref "IC3") (pin "77") (pinfunction "RE3/AD11/PMA13/P3C/REFO_77") (pintype "bidirectional"))
    )
    (net (code "152") (name "unconnected-(IC3-RE4{slash}AD12{slash}PMA12{slash}P3B-Pad76)") (class "Default")
      (node (ref "IC3") (pin "76") (pinfunction "RE4/AD12/PMA12/P3B_76") (pintype "bidirectional"))
    )
    (net (code "153") (name "unconnected-(IC3-RE5{slash}AD13{slash}PMA11{slash}P1C-Pad75)") (class "Default")
      (node (ref "IC3") (pin "75") (pinfunction "RE5/AD13/PMA11/P1C_75") (pintype "bidirectional"))
    )
    (net (code "154") (name "unconnected-(IC3-RE6{slash}AD14{slash}PMA10{slash}P1B-Pad74)") (class "Default")
      (node (ref "IC3") (pin "74") (pinfunction "RE6/AD14/PMA10/P1B_74") (pintype "bidirectional"))
    )
    (net (code "155") (name "unconnected-(IC3-RE7{slash}AD15{slash}PMA9{slash}ECCP2{slash}P2A-Pad73)") (class "Default")
      (node (ref "IC3") (pin "73") (pinfunction "RE7/AD15/PMA9/ECCP2/P2A_73") (pintype "bidirectional"))
    )
    (net (code "156") (name "unconnected-(IC3-RF5{slash}PMD2{slash}AN10{slash}C1INB{slash}CVREF-Pad15)") (class "Default")
      (node (ref "IC3") (pin "15") (pinfunction "RF5/PMD2/AN10/C1INB/CVREF_15") (pintype "bidirectional"))
    )
    (net (code "157") (name "unconnected-(IC3-RF6{slash}PMD1{slash}AN11{slash}C1INA-Pad14)") (class "Default")
      (node (ref "IC3") (pin "14") (pinfunction "RF6/PMD1/AN11/C1INA_14") (pintype "bidirectional"))
    )
    (net (code "158") (name "unconnected-(IC3-RF7{slash}PMD0{slash}~{SS1}{slash}C1OUT-Pad13)") (class "Default")
      (node (ref "IC3") (pin "13") (pinfunction "RF7/PMD0/~{SS1}/C1OUT_13") (pintype "bidirectional"))
    )
    (net (code "159") (name "unconnected-(IC3-RG1{slash}PMA7{slash}TX2{slash}CK2-Pad6)") (class "Default")
      (node (ref "IC3") (pin "6") (pinfunction "RG1/PMA7/TX2/CK2_6") (pintype "bidirectional"))
    )
    (net (code "160") (name "unconnected-(IC3-RG2{slash}PMA6{slash}RX2{slash}DT2-Pad7)") (class "Default")
      (node (ref "IC3") (pin "7") (pinfunction "RG2/PMA6/RX2/DT2_7") (pintype "bidirectional"))
    )
    (net (code "161") (name "unconnected-(IC3-RG3{slash}PMCS1{slash}CCP4{slash}P3D-Pad8)") (class "Default")
      (node (ref "IC3") (pin "8") (pinfunction "RG3/PMCS1/CCP4/P3D_8") (pintype "bidirectional"))
    )
    (net (code "162") (name "unconnected-(IC3-RG4{slash}PMCS2{slash}CCP5{slash}P1D-Pad10)") (class "Default")
      (node (ref "IC3") (pin "10") (pinfunction "RG4/PMCS2/CCP5/P1D_10") (pintype "bidirectional"))
    )
    (net (code "163") (name "unconnected-(IC3-RH0{slash}A16-Pad79)") (class "Default")
      (node (ref "IC3") (pin "79") (pinfunction "RH0/A16_79") (pintype "bidirectional"))
    )
    (net (code "164") (name "unconnected-(IC3-RH1{slash}A17-Pad80)") (class "Default")
      (node (ref "IC3") (pin "80") (pinfunction "RH1/A17_80") (pintype "bidirectional"))
    )
    (net (code "165") (name "unconnected-(IC3-RH2{slash}A18{slash}PMD7-Pad1)") (class "Default")
      (node (ref "IC3") (pin "1") (pinfunction "RH2/A18/PMD7_1") (pintype "bidirectional"))
    )
    (net (code "166") (name "unconnected-(IC3-RH3{slash}A19{slash}PMD6-Pad2)") (class "Default")
      (node (ref "IC3") (pin "2") (pinfunction "RH3/A19/PMD6_2") (pintype "bidirectional"))
    )
    (net (code "167") (name "unconnected-(IC3-RH4{slash}PMD3{slash}AN12{slash}P3C{slash}C2INC-Pad22)") (class "Default")
      (node (ref "IC3") (pin "22") (pinfunction "RH4/PMD3/AN12/P3C/C2INC_22") (pintype "bidirectional"))
    )
    (net (code "168") (name "unconnected-(IC3-RH5{slash}PMBE{slash}AN13{slash}P3B{slash}C2IND-Pad21)") (class "Default")
      (node (ref "IC3") (pin "21") (pinfunction "RH5/PMBE/AN13/P3B/C2IND_21") (pintype "bidirectional"))
    )
    (net (code "169") (name "unconnected-(IC3-RH6{slash}PMRD{slash}AN14{slash}P1C{slash}C1INC-Pad20)") (class "Default")
      (node (ref "IC3") (pin "20") (pinfunction "RH6/PMRD/AN14/P1C/C1INC_20") (pintype "bidirectional"))
    )
    (net (code "170") (name "unconnected-(IC3-RH7{slash}PMWR{slash}AN15{slash}P1B-Pad19)") (class "Default")
      (node (ref "IC3") (pin "19") (pinfunction "RH7/PMWR/AN15/P1B_19") (pintype "bidirectional"))
    )
    (net (code "171") (name "unconnected-(IC3-RJ0{slash}ALE-Pad62)") (class "Default")
      (node (ref "IC3") (pin "62") (pinfunction "RJ0/ALE_62") (pintype "bidirectional"))
    )
    (net (code "172") (name "unconnected-(IC3-RJ1{slash}~{OE}-Pad61)") (class "Default")
      (node (ref "IC3") (pin "61") (pinfunction "RJ1/~{OE}_61") (pintype "bidirectional"))
    )
    (net (code "173") (name "unconnected-(IC3-RJ4{slash}BA0-Pad39)") (class "Default")
      (node (ref "IC3") (pin "39") (pinfunction "RJ4/BA0_39") (pintype "bidirectional"))
    )
    (net (code "174") (name "unconnected-(IC3-RJ7{slash}~{UB}-Pad42)") (class "Default")
      (node (ref "IC3") (pin "42") (pinfunction "RJ7/~{UB}_42") (pintype "bidirectional"))
    )
    (net (code "175") (name "unconnected-(IC5-CLK1-Pad18)") (class "Default")
      (node (ref "IC5") (pin "18") (pinfunction "CLK1_18") (pintype "bidirectional"))
    )
    (net (code "176") (name "unconnected-(IC5-CLK2-Pad21)") (class "Default")
      (node (ref "IC5") (pin "21") (pinfunction "CLK2_21") (pintype "bidirectional"))
    )
    (net (code "177") (name "unconnected-(IC5-CLK3-Pad22)") (class "Default")
      (node (ref "IC5") (pin "22") (pinfunction "CLK3_22") (pintype "bidirectional"))
    )
    (net (code "178") (name "unconnected-(IC5-CLK4-Pad91)") (class "Default")
      (node (ref "IC5") (pin "91") (pinfunction "CLK4_91") (pintype "bidirectional"))
    )
    (net (code "179") (name "unconnected-(IC5-IO42-Pad42)") (class "Default")
      (node (ref "IC5") (pin "42") (pinfunction "IO42_42") (pintype "bidirectional"))
    )
    (net (code "180") (name "unconnected-(IC5-IO43-Pad43)") (class "Default")
      (node (ref "IC5") (pin "43") (pinfunction "IO43_43") (pintype "bidirectional"))
    )
    (net (code "181") (name "unconnected-(IC5-IO44-Pad44)") (class "Default")
      (node (ref "IC5") (pin "44") (pinfunction "IO44_44") (pintype "bidirectional"))
    )
    (net (code "182") (name "unconnected-(IC5-IO45-Pad45)") (class "Default")
      (node (ref "IC5") (pin "45") (pinfunction "IO45_45") (pintype "bidirectional"))
    )
    (net (code "183") (name "unconnected-(IC5-IO47-Pad47)") (class "Default")
      (node (ref "IC5") (pin "47") (pinfunction "IO47_47") (pintype "bidirectional"))
    )
    (net (code "184") (name "unconnected-(IC5-IO51-Pad51)") (class "Default")
      (node (ref "IC5") (pin "51") (pinfunction "IO51_51") (pintype "bidirectional"))
    )
    (net (code "185") (name "unconnected-(IC5-IO52-Pad52)") (class "Default")
      (node (ref "IC5") (pin "52") (pinfunction "IO52_52") (pintype "bidirectional"))
    )
    (net (code "186") (name "unconnected-(IC5-IO64-Pad64)") (class "Default")
      (node (ref "IC5") (pin "64") (pinfunction "IO64_64") (pintype "bidirectional"))
    )
    (net (code "187") (name "unconnected-(IC5-IO65-Pad65)") (class "Default")
      (node (ref "IC5") (pin "65") (pinfunction "IO65_65") (pintype "bidirectional"))
    )
    (net (code "188") (name "unconnected-(IC5-IO67-Pad67)") (class "Default")
      (node (ref "IC5") (pin "67") (pinfunction "IO67_67") (pintype "bidirectional"))
    )
    (net (code "189") (name "unconnected-(IC5-IO69-Pad69)") (class "Default")
      (node (ref "IC5") (pin "69") (pinfunction "IO69_69") (pintype "bidirectional"))
    )
    (net (code "190") (name "unconnected-(IC5-IO70-Pad70)") (class "Default")
      (node (ref "IC5") (pin "70") (pinfunction "IO70_70") (pintype "bidirectional"))
    )
    (net (code "191") (name "unconnected-(IC5-IO101-Pad101)") (class "Default")
      (node (ref "IC5") (pin "101") (pinfunction "IO101_101") (pintype "bidirectional"))
    )
    (net (code "192") (name "unconnected-(IC5-IO119-Pad119)") (class "Default")
      (node (ref "IC5") (pin "119") (pinfunction "IO119_119") (pintype "bidirectional"))
    )
    (net (code "193") (name "unconnected-(IC5-IO120-Pad120)") (class "Default")
      (node (ref "IC5") (pin "120") (pinfunction "IO120_120") (pintype "bidirectional"))
    )
  )
)
